# hp_main.net
KiCad netlist of a schematic drawn in Altium Designer
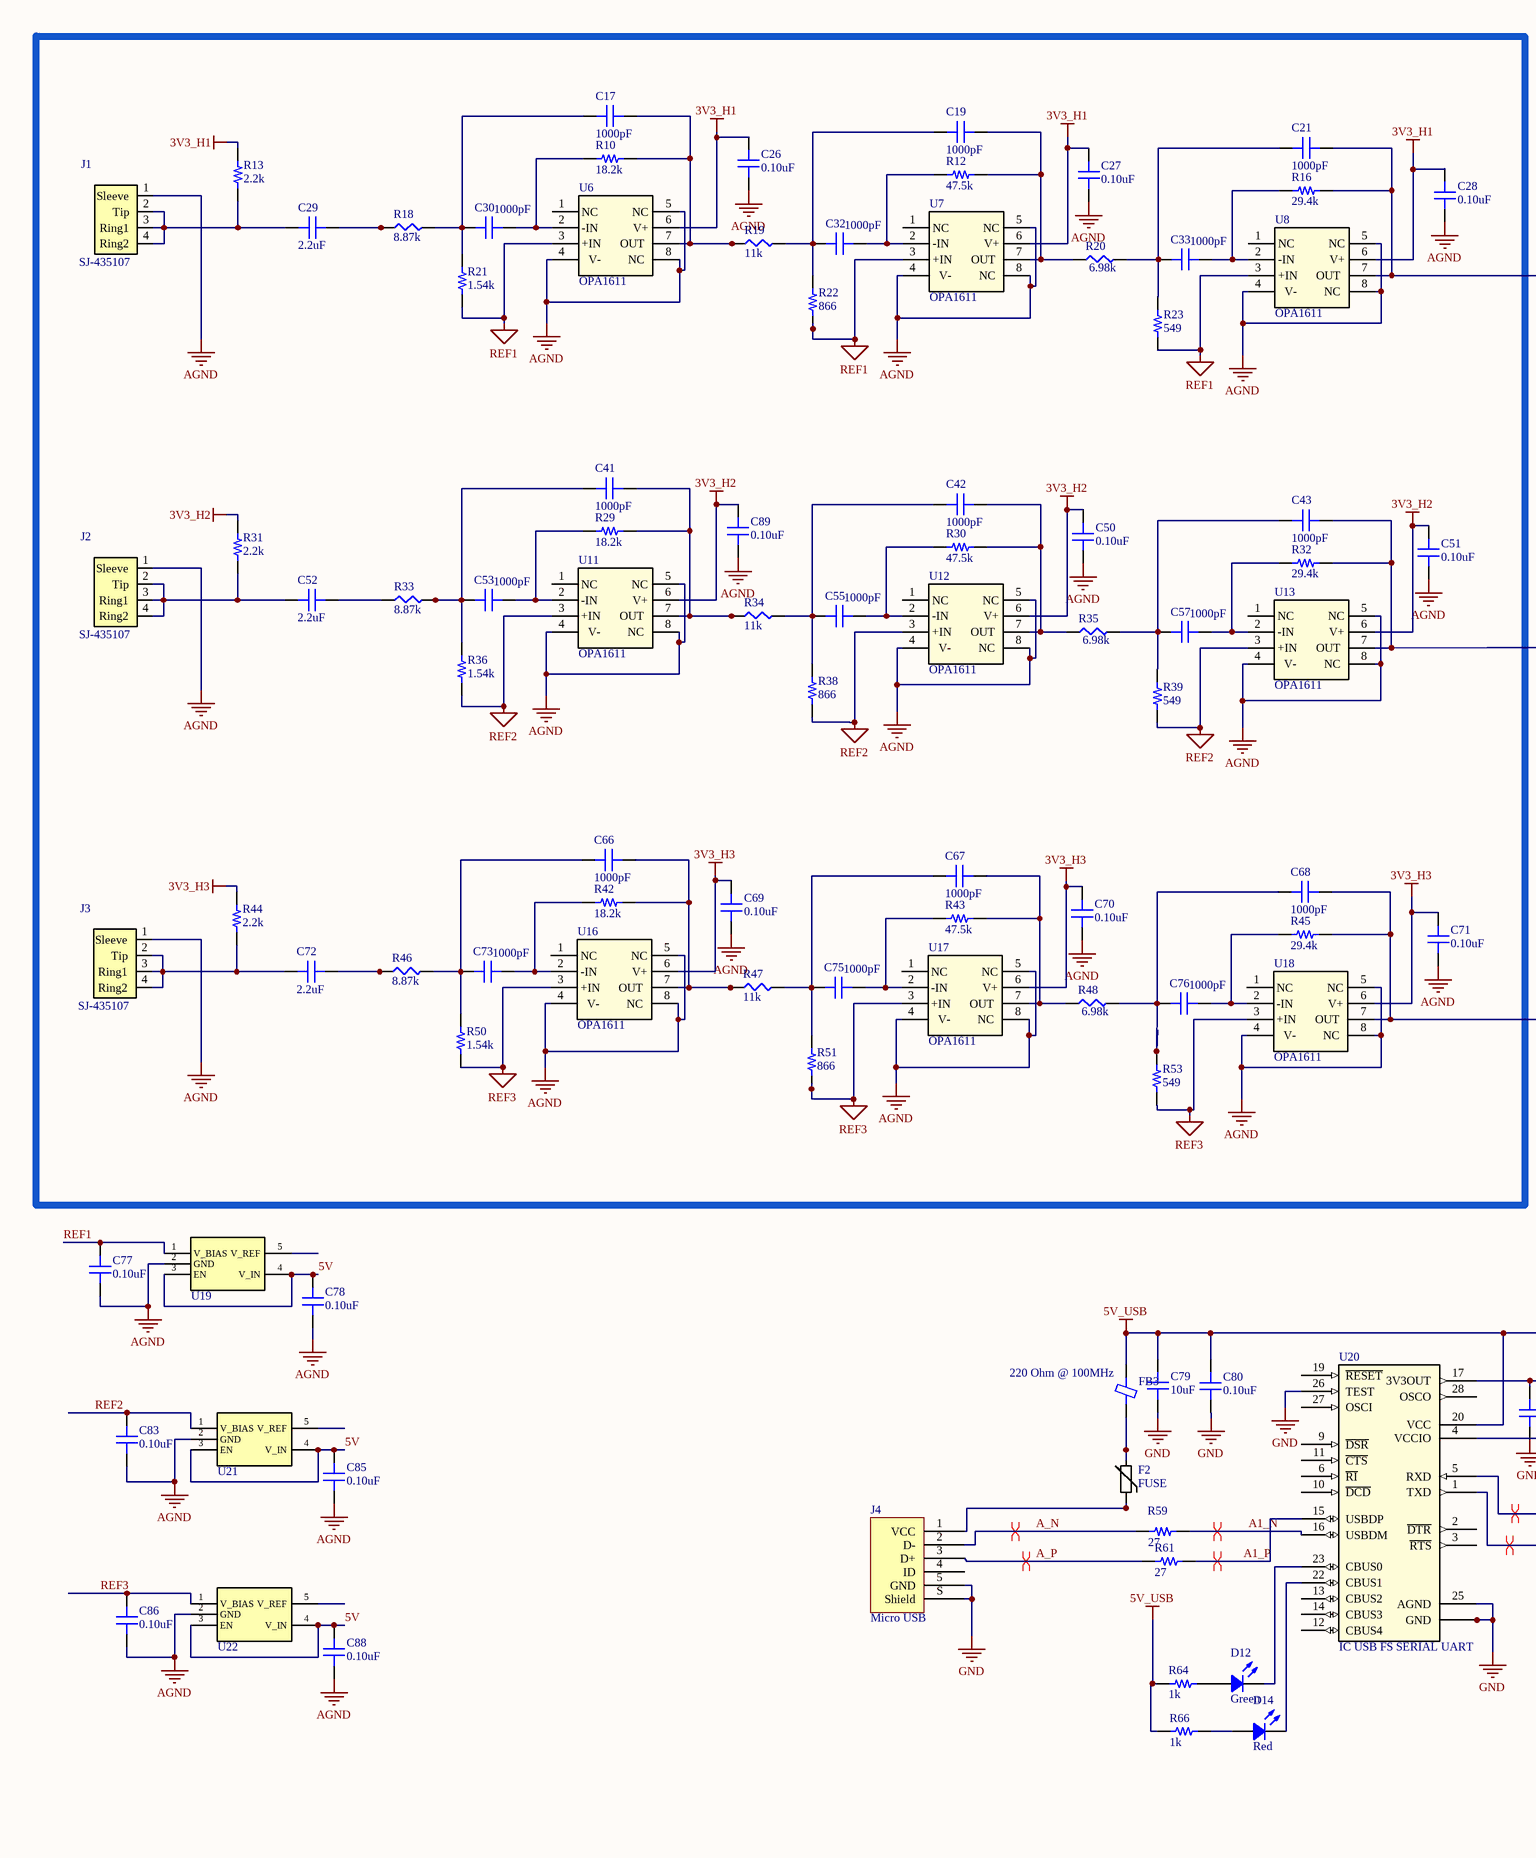
[diagram p0: hp_main.SchDoc, left]
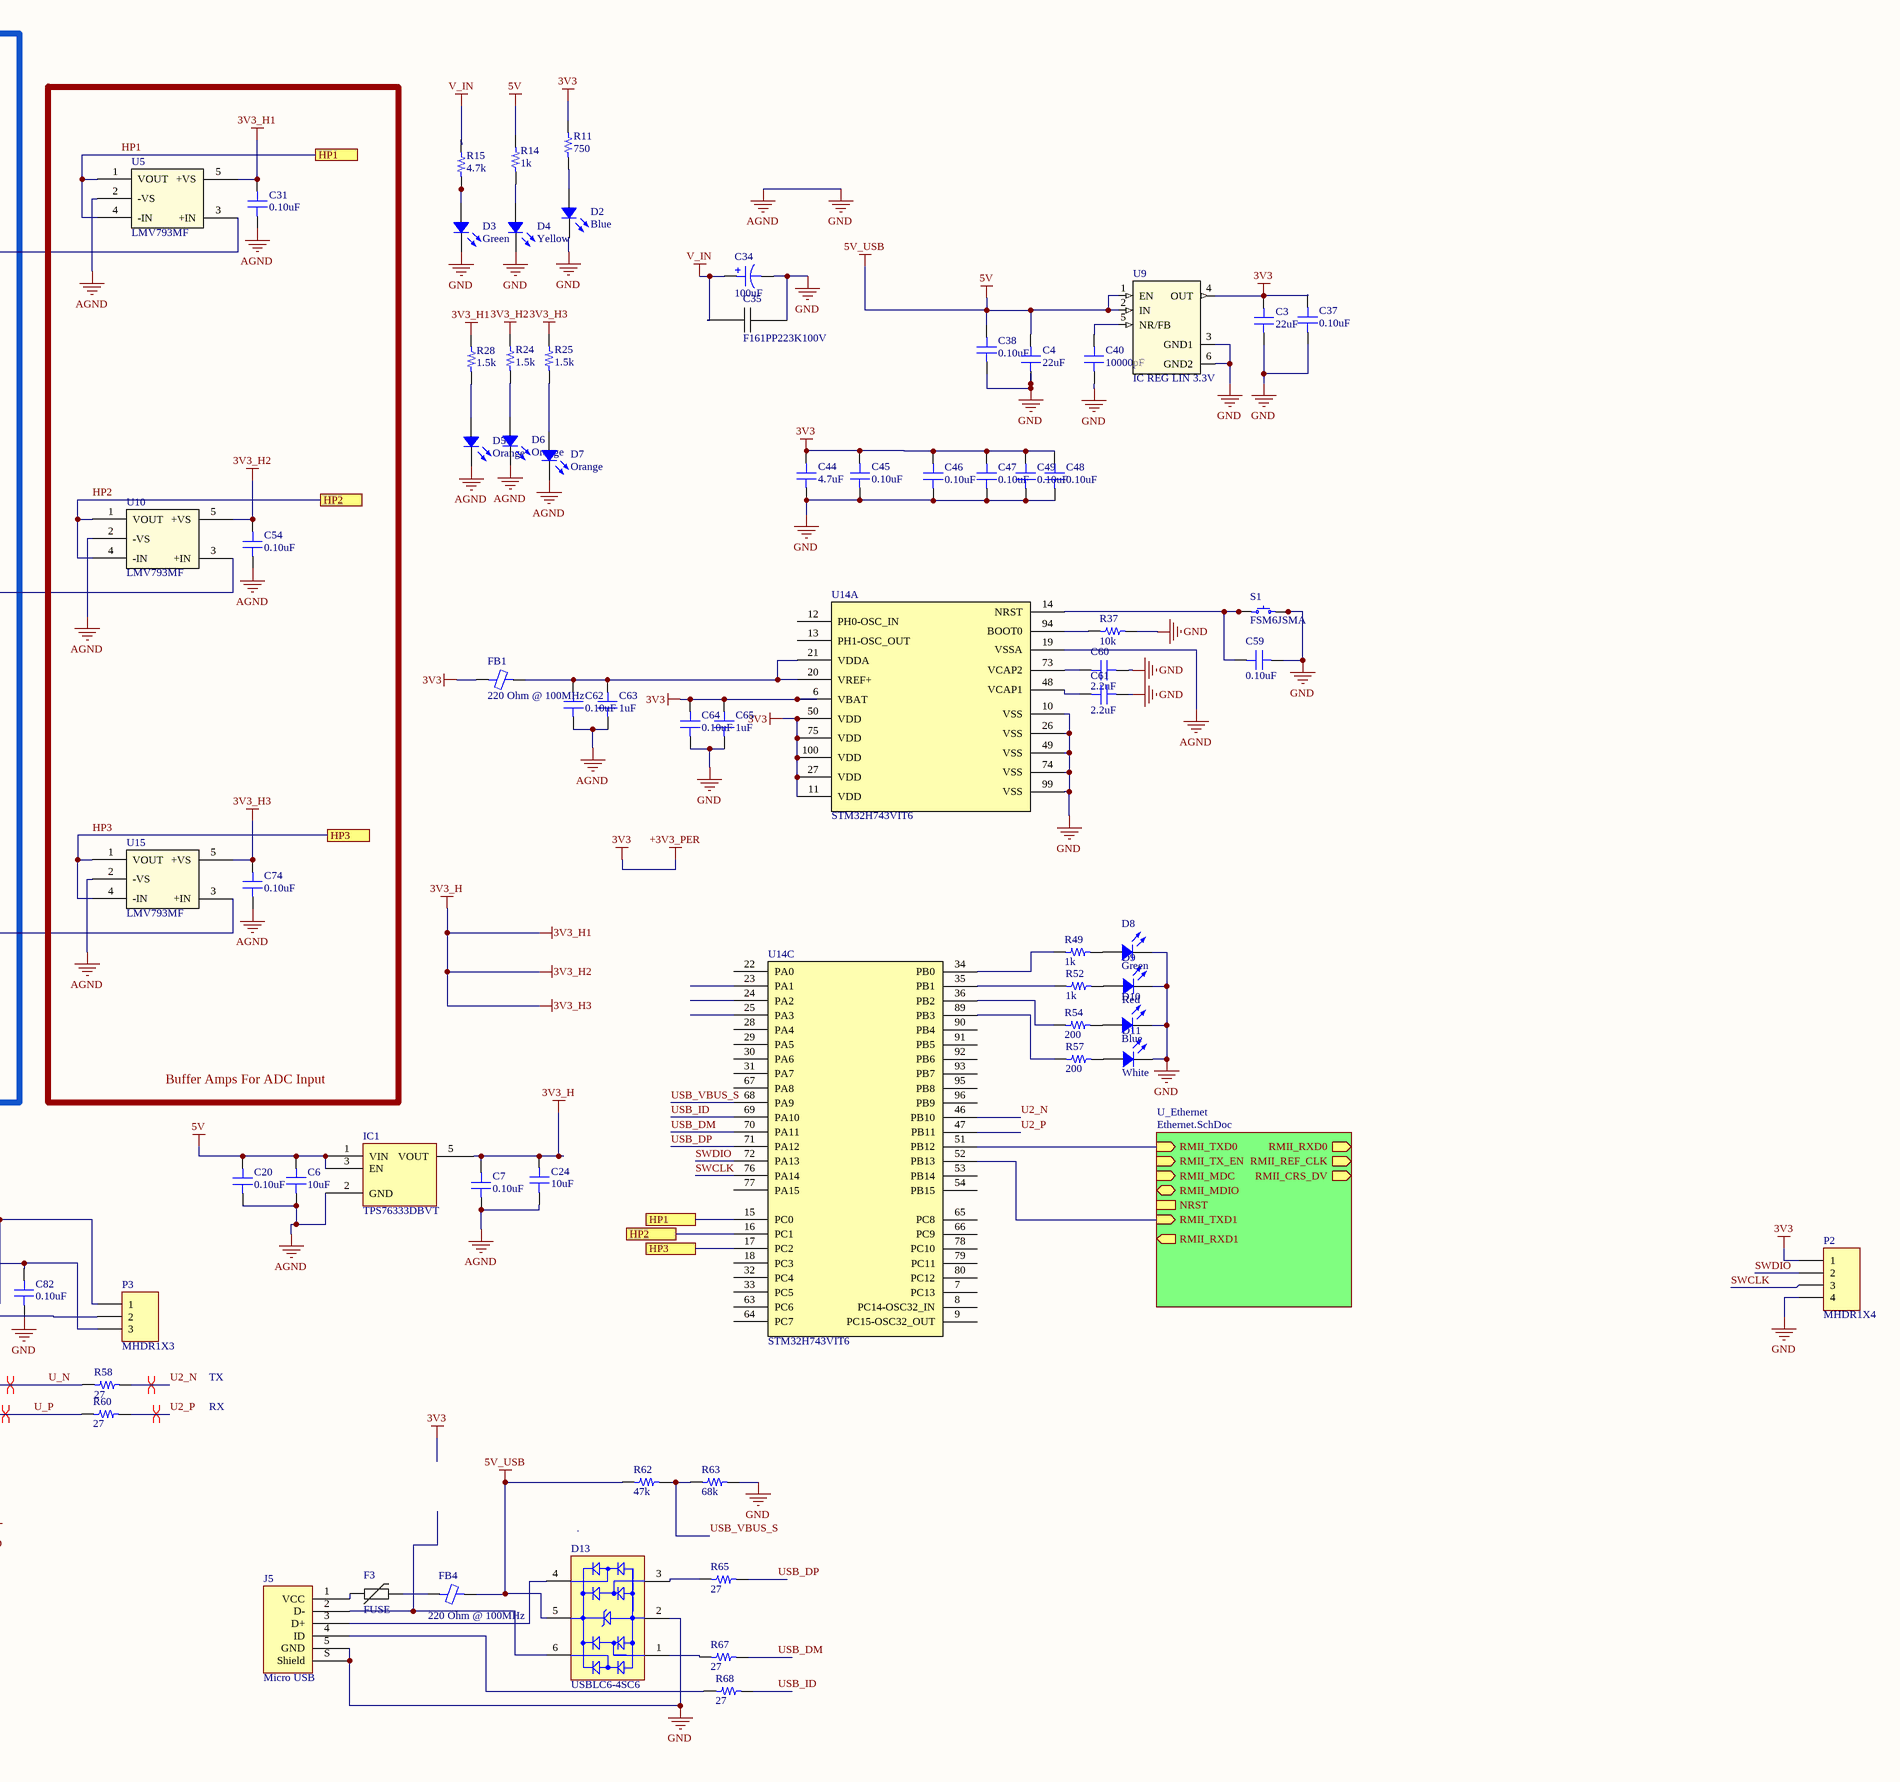
[diagram p1: hp_main.SchDoc, right]

(export (version "E")
  (design (tool "Eeschema 10.0.6"))
  (components
    (comp (ref "C3")
      (value "22uF")
      (footprint "CAP 1206/3216")
      (description "CAP CER 22UF 16V X6S 1206")
      (fields
        (field (name "PART NUMBER") "GRT31CC81C226KE01L")
        (field (name "MANUFACTURER") "Murata Electronics North America")
      )
      (libsource (lib "Celestial Library Database") (part "Capacitor"))
    )
    (comp (ref "C4")
      (value "22uF")
      (footprint "CAP 1206/3216")
      (description "CAP CER 22UF 16V X6S 1206")
      (fields
        (field (name "PART NUMBER") "GRT31CC81C226KE01L")
        (field (name "MANUFACTURER") "Murata Electronics North America")
      )
      (libsource (lib "Celestial Library Database") (part "Capacitor"))
    )
    (comp (ref "C6")
      (value "10uF")
      (footprint "CAP 1206/3216")
      (description "CAP CER 10UF 16V X5R 1206")
      (fields
        (field (name "PART NUMBER") "GRT31CR61C106KE01L")
        (field (name "MANUFACTURER") "Murata Electronics North America")
      )
      (libsource (lib "Celestial Library Database") (part "Capacitor"))
    )
    (comp (ref "C7")
      (value "0.10uF")
      (footprint "CAP 0805/2012")
      (description "CAP CER 0.1UF 100V X7R 0805")
      (fields
        (field (name "PART NUMBER") "CL21B104KCFSFNE")
        (field (name "MANUFACTURER") "Samsung Electro-Mechanics America, Inc.")
      )
      (libsource (lib "Celestial Library Database") (part "Capacitor"))
    )
    (comp (ref "C17")
      (value "1000pF")
      (footprint "CAP 0603/1608")
      (description "CAP CER 1000PF 25V NP0 0603")
      (fields (field (name "PART NUMBER") "C0603C102F3GACTU") (field (name "MANUFACTURER") "Kemet"))
      (libsource (lib "Celestial Library Database") (part "Capacitor"))
    )
    (comp (ref "C19")
      (value "1000pF")
      (footprint "CAP 0603/1608")
      (description "CAP CER 1000PF 25V NP0 0603")
      (fields (field (name "PART NUMBER") "C0603C102F3GACTU") (field (name "MANUFACTURER") "Kemet"))
      (libsource (lib "Celestial Library Database") (part "Capacitor"))
    )
    (comp (ref "C20")
      (value "0.10uF")
      (footprint "CAP 0805/2012")
      (description "CAP CER 0.1UF 100V X7R 0805")
      (fields
        (field (name "PART NUMBER") "CL21B104KCFSFNE")
        (field (name "MANUFACTURER") "Samsung Electro-Mechanics America, Inc.")
      )
      (libsource (lib "Celestial Library Database") (part "Capacitor"))
    )
    (comp (ref "C21")
      (value "1000pF")
      (footprint "CAP 0603/1608")
      (description "CAP CER 1000PF 25V NP0 0603")
      (fields (field (name "PART NUMBER") "C0603C102F3GACTU") (field (name "MANUFACTURER") "Kemet"))
      (libsource (lib "Celestial Library Database") (part "Capacitor"))
    )
    (comp (ref "C24")
      (value "10uF")
      (footprint "CAP 1206/3216")
      (description "CAP CER 10UF 16V X5R 1206")
      (fields
        (field (name "PART NUMBER") "GRT31CR61C106KE01L")
        (field (name "MANUFACTURER") "Murata Electronics North America")
      )
      (libsource (lib "Celestial Library Database") (part "Capacitor"))
    )
    (comp (ref "C26")
      (value "0.10uF")
      (footprint "CAP 0805/2012")
      (description "CAP CER 0.1UF 100V X7R 0805")
      (fields
        (field (name "PART NUMBER") "CL21B104KCFSFNE")
        (field (name "MANUFACTURER") "Samsung Electro-Mechanics America, Inc.")
      )
      (libsource (lib "Celestial Library Database") (part "Capacitor"))
    )
    (comp (ref "C27")
      (value "0.10uF")
      (footprint "CAP 0805/2012")
      (description "CAP CER 0.1UF 100V X7R 0805")
      (fields
        (field (name "PART NUMBER") "CL21B104KCFSFNE")
        (field (name "MANUFACTURER") "Samsung Electro-Mechanics America, Inc.")
      )
      (libsource (lib "Celestial Library Database") (part "Capacitor"))
    )
    (comp (ref "C28")
      (value "0.10uF")
      (footprint "CAP 0805/2012")
      (description "CAP CER 0.1UF 100V X7R 0805")
      (fields
        (field (name "PART NUMBER") "CL21B104KCFSFNE")
        (field (name "MANUFACTURER") "Samsung Electro-Mechanics America, Inc.")
      )
      (libsource (lib "Celestial Library Database") (part "Capacitor"))
    )
    (comp (ref "C29")
      (value "2.2uF")
      (footprint "CAP 0805/2012")
      (description "CAP CER 2.2UF 16V X7R 0805")
      (fields (field (name "PART NUMBER") "C0805C225K4RACTU") (field (name "MANUFACTURER") "Kemet"))
      (libsource (lib "Celestial Library Database") (part "Capacitor"))
    )
    (comp (ref "C30")
      (value "1000pF")
      (footprint "CAP 0603/1608")
      (description "CAP CER 1000PF 25V NP0 0603")
      (fields (field (name "PART NUMBER") "C0603C102F3GACTU") (field (name "MANUFACTURER") "Kemet"))
      (libsource (lib "Celestial Library Database") (part "Capacitor"))
    )
    (comp (ref "C31")
      (value "0.10uF")
      (footprint "CAP 0805/2012")
      (description "CAP CER 0.1UF 100V X7R 0805")
      (fields
        (field (name "PART NUMBER") "CL21B104KCFSFNE")
        (field (name "MANUFACTURER") "Samsung Electro-Mechanics America, Inc.")
      )
      (libsource (lib "Celestial Library Database") (part "Capacitor"))
    )
    (comp (ref "C32")
      (value "1000pF")
      (footprint "CAP 0603/1608")
      (description "CAP CER 1000PF 25V NP0 0603")
      (fields (field (name "PART NUMBER") "C0603C102F3GACTU") (field (name "MANUFACTURER") "Kemet"))
      (libsource (lib "Celestial Library Database") (part "Capacitor"))
    )
    (comp (ref "C33")
      (value "1000pF")
      (footprint "CAP 0603/1608")
      (description "CAP CER 1000PF 25V NP0 0603")
      (fields (field (name "PART NUMBER") "C0603C102F3GACTU") (field (name "MANUFACTURER") "Kemet"))
      (libsource (lib "Celestial Library Database") (part "Capacitor"))
    )
    (comp (ref "C34")
      (value "100uF")
      (footprint "CAP ALUM 6.6MM")
      (description "CAP ALUM 100UF 20% 25V SMD")
      (fields
        (field (name "PART NUMBER") "EEE-1EA101XP")
        (field (name "MANUFACTURER") "Panasonic Electronic Components")
      )
      (libsource (lib "Celestial Library Database") (part "Polarised Capacitor"))
    )
    (comp (ref "C35")
      (value "F161PP223K100V")
      (footprint "F161PP223K100V")
      (libsource (lib "rover_schematic_libraries") (part "F161PP223K100V"))
    )
    (comp (ref "C37")
      (value "0.10uF")
      (footprint "CAP 0805/2012")
      (description "CAP CER 0.1UF 100V X7R 0805")
      (fields
        (field (name "PART NUMBER") "CL21B104KCFSFNE")
        (field (name "MANUFACTURER") "Samsung Electro-Mechanics America, Inc.")
      )
      (libsource (lib "Celestial Library Database") (part "Capacitor"))
    )
    (comp (ref "C38")
      (value "0.10uF")
      (footprint "CAP 0805/2012")
      (description "CAP CER 0.1UF 100V X7R 0805")
      (fields
        (field (name "PART NUMBER") "CL21B104KCFSFNE")
        (field (name "MANUFACTURER") "Samsung Electro-Mechanics America, Inc.")
      )
      (libsource (lib "Celestial Library Database") (part "Capacitor"))
    )
    (comp (ref "C40")
      (value "10000pF")
      (footprint "CAP 0805/2012")
      (description "CAP CER 10000PF 250V X7R 0805")
      (fields
        (field (name "PART NUMBER") "GCJ21BR72E103KXJ3L")
        (field (name "MANUFACTURER") "Murata Electronics North America")
      )
      (libsource (lib "Celestial Library Database") (part "Capacitor"))
    )
    (comp (ref "C41")
      (value "1000pF")
      (footprint "CAP 0603/1608")
      (description "CAP CER 1000PF 25V NP0 0603")
      (fields (field (name "PART NUMBER") "C0603C102F3GACTU") (field (name "MANUFACTURER") "Kemet"))
      (libsource (lib "Celestial Library Database") (part "Capacitor"))
    )
    (comp (ref "C42")
      (value "1000pF")
      (footprint "CAP 0603/1608")
      (description "CAP CER 1000PF 25V NP0 0603")
      (fields (field (name "PART NUMBER") "C0603C102F3GACTU") (field (name "MANUFACTURER") "Kemet"))
      (libsource (lib "Celestial Library Database") (part "Capacitor"))
    )
    (comp (ref "C43")
      (value "1000pF")
      (footprint "CAP 0603/1608")
      (description "CAP CER 1000PF 25V NP0 0603")
      (fields (field (name "PART NUMBER") "C0603C102F3GACTU") (field (name "MANUFACTURER") "Kemet"))
      (libsource (lib "Celestial Library Database") (part "Capacitor"))
    )
    (comp (ref "C44")
      (value "4.7uF")
      (footprint "CAP 0805/2012")
      (description "CAP CER 4.7UF 35V X5R 0805")
      (fields
        (field (name "PART NUMBER") "GRM219R6YA475KA73D")
        (field (name "MANUFACTURER") "Murata Electronics North America")
      )
      (libsource (lib "Celestial Library Database") (part "Capacitor"))
    )
    (comp (ref "C45")
      (value "0.10uF")
      (footprint "CAP 0805/2012")
      (description "CAP CER 0.1UF 100V X7R 0805")
      (fields
        (field (name "PART NUMBER") "CGA4J2X7R2A104K125AE")
        (field (name "MANUFACTURER") "TDK Corporation")
      )
      (libsource (lib "Celestial Library Database") (part "Capacitor"))
    )
    (comp (ref "C46")
      (value "0.10uF")
      (footprint "CAP 0805/2012")
      (description "CAP CER 0.1UF 100V X7R 0805")
      (fields
        (field (name "PART NUMBER") "CGA4J2X7R2A104K125AE")
        (field (name "MANUFACTURER") "TDK Corporation")
      )
      (libsource (lib "Celestial Library Database") (part "Capacitor"))
    )
    (comp (ref "C47")
      (value "0.10uF")
      (footprint "CAP 0805/2012")
      (description "CAP CER 0.1UF 100V X7R 0805")
      (fields
        (field (name "PART NUMBER") "CGA4J2X7R2A104K125AE")
        (field (name "MANUFACTURER") "TDK Corporation")
      )
      (libsource (lib "Celestial Library Database") (part "Capacitor"))
    )
    (comp (ref "C48")
      (value "0.10uF")
      (footprint "CAP 0805/2012")
      (description "CAP CER 0.1UF 100V X7R 0805")
      (fields
        (field (name "PART NUMBER") "CGA4J2X7R2A104K125AE")
        (field (name "MANUFACTURER") "TDK Corporation")
      )
      (libsource (lib "Celestial Library Database") (part "Capacitor"))
    )
    (comp (ref "C49")
      (value "0.10uF")
      (footprint "CAP 0805/2012")
      (description "CAP CER 0.1UF 100V X7R 0805")
      (fields
        (field (name "PART NUMBER") "CGA4J2X7R2A104K125AE")
        (field (name "MANUFACTURER") "TDK Corporation")
      )
      (libsource (lib "Celestial Library Database") (part "Capacitor"))
    )
    (comp (ref "C50")
      (value "0.10uF")
      (footprint "CAP 0805/2012")
      (description "CAP CER 0.1UF 100V X7R 0805")
      (fields
        (field (name "PART NUMBER") "CL21B104KCFSFNE")
        (field (name "MANUFACTURER") "Samsung Electro-Mechanics America, Inc.")
      )
      (libsource (lib "Celestial Library Database") (part "Capacitor"))
    )
    (comp (ref "C51")
      (value "0.10uF")
      (footprint "CAP 0805/2012")
      (description "CAP CER 0.1UF 100V X7R 0805")
      (fields
        (field (name "PART NUMBER") "CL21B104KCFSFNE")
        (field (name "MANUFACTURER") "Samsung Electro-Mechanics America, Inc.")
      )
      (libsource (lib "Celestial Library Database") (part "Capacitor"))
    )
    (comp (ref "C52")
      (value "2.2uF")
      (footprint "CAP 0805/2012")
      (description "CAP CER 2.2UF 16V X7R 0805")
      (fields (field (name "PART NUMBER") "C0805C225K4RACTU") (field (name "MANUFACTURER") "Kemet"))
      (libsource (lib "Celestial Library Database") (part "Capacitor"))
    )
    (comp (ref "C53")
      (value "1000pF")
      (footprint "CAP 0603/1608")
      (description "CAP CER 1000PF 25V NP0 0603")
      (fields (field (name "PART NUMBER") "C0603C102F3GACTU") (field (name "MANUFACTURER") "Kemet"))
      (libsource (lib "Celestial Library Database") (part "Capacitor"))
    )
    (comp (ref "C54")
      (value "0.10uF")
      (footprint "CAP 0805/2012")
      (description "CAP CER 0.1UF 100V X7R 0805")
      (fields
        (field (name "PART NUMBER") "CL21B104KCFSFNE")
        (field (name "MANUFACTURER") "Samsung Electro-Mechanics America, Inc.")
      )
      (libsource (lib "Celestial Library Database") (part "Capacitor"))
    )
    (comp (ref "C55")
      (value "1000pF")
      (footprint "CAP 0603/1608")
      (description "CAP CER 1000PF 25V NP0 0603")
      (fields (field (name "PART NUMBER") "C0603C102F3GACTU") (field (name "MANUFACTURER") "Kemet"))
      (libsource (lib "Celestial Library Database") (part "Capacitor"))
    )
    (comp (ref "C57")
      (value "1000pF")
      (footprint "CAP 0603/1608")
      (description "CAP CER 1000PF 25V NP0 0603")
      (fields (field (name "PART NUMBER") "C0603C102F3GACTU") (field (name "MANUFACTURER") "Kemet"))
      (libsource (lib "Celestial Library Database") (part "Capacitor"))
    )
    (comp (ref "C59")
      (value "0.10uF")
      (footprint "CAP 0805/2012")
      (description "CAP CER 0.1UF 100V X7R 0805")
      (fields
        (field (name "PART NUMBER") "CL21B104KCFSFNE")
        (field (name "MANUFACTURER") "Samsung Electro-Mechanics America, Inc.")
      )
      (libsource (lib "Celestial Library Database") (part "Capacitor"))
    )
    (comp (ref "C60")
      (value "2.2uF")
      (footprint "CAP 0805/2012")
      (description "CAP CER 2.2UF 50V X7R 0805")
      (fields
        (field (name "PART NUMBER") "C2012X7R1H225K125AC")
        (field (name "MANUFACTURER") "TDK Corporation")
      )
      (libsource (lib "Celestial Library Database") (part "Capacitor"))
    )
    (comp (ref "C61")
      (value "2.2uF")
      (footprint "CAP 0805/2012")
      (description "CAP CER 2.2UF 50V X7R 0805")
      (fields
        (field (name "PART NUMBER") "C2012X7R1H225K125AC")
        (field (name "MANUFACTURER") "TDK Corporation")
      )
      (libsource (lib "Celestial Library Database") (part "Capacitor"))
    )
    (comp (ref "C62")
      (value "0.10uF")
      (footprint "CAP 0805/2012")
      (description "CAP CER 0.1UF 100V X7R 0805")
      (fields
        (field (name "PART NUMBER") "CGA4J2X7R2A104K125AE")
        (field (name "MANUFACTURER") "TDK Corporation")
      )
      (libsource (lib "Celestial Library Database") (part "Capacitor"))
    )
    (comp (ref "C63")
      (value "1uF")
      (footprint "CAP 0805/2012")
      (description "CAP CER 1UF 25V X5R 0805")
      (fields
        (field (name "PART NUMBER") "GRM216R61E105KA12D")
        (field (name "MANUFACTURER") "Murata Electronics North America")
      )
      (libsource (lib "Celestial Library Database") (part "Capacitor"))
    )
    (comp (ref "C64")
      (value "0.10uF")
      (footprint "CAP 0805/2012")
      (description "CAP CER 0.1UF 100V X7R 0805")
      (fields
        (field (name "PART NUMBER") "CGA4J2X7R2A104K125AE")
        (field (name "MANUFACTURER") "TDK Corporation")
      )
      (libsource (lib "Celestial Library Database") (part "Capacitor"))
    )
    (comp (ref "C65")
      (value "1uF")
      (footprint "CAP 0805/2012")
      (description "CAP CER 1UF 25V X5R 0805")
      (fields
        (field (name "PART NUMBER") "GRM216R61E105KA12D")
        (field (name "MANUFACTURER") "Murata Electronics North America")
      )
      (libsource (lib "Celestial Library Database") (part "Capacitor"))
    )
    (comp (ref "C66")
      (value "1000pF")
      (footprint "CAP 0603/1608")
      (description "CAP CER 1000PF 25V NP0 0603")
      (fields (field (name "PART NUMBER") "C0603C102F3GACTU") (field (name "MANUFACTURER") "Kemet"))
      (libsource (lib "Celestial Library Database") (part "Capacitor"))
    )
    (comp (ref "C67")
      (value "1000pF")
      (footprint "CAP 0603/1608")
      (description "CAP CER 1000PF 25V NP0 0603")
      (fields (field (name "PART NUMBER") "C0603C102F3GACTU") (field (name "MANUFACTURER") "Kemet"))
      (libsource (lib "Celestial Library Database") (part "Capacitor"))
    )
    (comp (ref "C68")
      (value "1000pF")
      (footprint "CAP 0603/1608")
      (description "CAP CER 1000PF 25V NP0 0603")
      (fields (field (name "PART NUMBER") "C0603C102F3GACTU") (field (name "MANUFACTURER") "Kemet"))
      (libsource (lib "Celestial Library Database") (part "Capacitor"))
    )
    (comp (ref "C69")
      (value "0.10uF")
      (footprint "CAP 0805/2012")
      (description "CAP CER 0.1UF 100V X7R 0805")
      (fields
        (field (name "PART NUMBER") "CL21B104KCFSFNE")
        (field (name "MANUFACTURER") "Samsung Electro-Mechanics America, Inc.")
      )
      (libsource (lib "Celestial Library Database") (part "Capacitor"))
    )
    (comp (ref "C70")
      (value "0.10uF")
      (footprint "CAP 0805/2012")
      (description "CAP CER 0.1UF 100V X7R 0805")
      (fields
        (field (name "PART NUMBER") "CL21B104KCFSFNE")
        (field (name "MANUFACTURER") "Samsung Electro-Mechanics America, Inc.")
      )
      (libsource (lib "Celestial Library Database") (part "Capacitor"))
    )
    (comp (ref "C71")
      (value "0.10uF")
      (footprint "CAP 0805/2012")
      (description "CAP CER 0.1UF 100V X7R 0805")
      (fields
        (field (name "PART NUMBER") "CL21B104KCFSFNE")
        (field (name "MANUFACTURER") "Samsung Electro-Mechanics America, Inc.")
      )
      (libsource (lib "Celestial Library Database") (part "Capacitor"))
    )
    (comp (ref "C72")
      (value "2.2uF")
      (footprint "CAP 0805/2012")
      (description "CAP CER 2.2UF 16V X7R 0805")
      (fields (field (name "PART NUMBER") "C0805C225K4RACTU") (field (name "MANUFACTURER") "Kemet"))
      (libsource (lib "Celestial Library Database") (part "Capacitor"))
    )
    (comp (ref "C73")
      (value "1000pF")
      (footprint "CAP 0603/1608")
      (description "CAP CER 1000PF 25V NP0 0603")
      (fields (field (name "PART NUMBER") "C0603C102F3GACTU") (field (name "MANUFACTURER") "Kemet"))
      (libsource (lib "Celestial Library Database") (part "Capacitor"))
    )
    (comp (ref "C74")
      (value "0.10uF")
      (footprint "CAP 0805/2012")
      (description "CAP CER 0.1UF 100V X7R 0805")
      (fields
        (field (name "PART NUMBER") "CL21B104KCFSFNE")
        (field (name "MANUFACTURER") "Samsung Electro-Mechanics America, Inc.")
      )
      (libsource (lib "Celestial Library Database") (part "Capacitor"))
    )
    (comp (ref "C75")
      (value "1000pF")
      (footprint "CAP 0603/1608")
      (description "CAP CER 1000PF 25V NP0 0603")
      (fields (field (name "PART NUMBER") "C0603C102F3GACTU") (field (name "MANUFACTURER") "Kemet"))
      (libsource (lib "Celestial Library Database") (part "Capacitor"))
    )
    (comp (ref "C76")
      (value "1000pF")
      (footprint "CAP 0603/1608")
      (description "CAP CER 1000PF 25V NP0 0603")
      (fields (field (name "PART NUMBER") "C0603C102F3GACTU") (field (name "MANUFACTURER") "Kemet"))
      (libsource (lib "Celestial Library Database") (part "Capacitor"))
    )
    (comp (ref "C77")
      (value "0.10uF")
      (footprint "CAP 0805/2012")
      (description "CAP CER 0.1UF 100V X7R 0805")
      (fields
        (field (name "PART NUMBER") "CL21B104KCFSFNE")
        (field (name "MANUFACTURER") "Samsung Electro-Mechanics America, Inc.")
      )
      (libsource (lib "Celestial Library Database") (part "Capacitor"))
    )
    (comp (ref "C78")
      (value "0.10uF")
      (footprint "CAP 0805/2012")
      (description "CAP CER 0.1UF 100V X7R 0805")
      (fields
        (field (name "PART NUMBER") "CL21B104KCFSFNE")
        (field (name "MANUFACTURER") "Samsung Electro-Mechanics America, Inc.")
      )
      (libsource (lib "Celestial Library Database") (part "Capacitor"))
    )
    (comp (ref "C79")
      (value "10uF")
      (footprint "CAP 1206/3216")
      (description "CAP CER 10UF 16V X5R 1206")
      (fields
        (field (name "PART NUMBER") "GRT31CR61C106KE01L")
        (field (name "MANUFACTURER") "Murata Electronics North America")
      )
      (libsource (lib "Celestial Library Database") (part "Capacitor"))
    )
    (comp (ref "C80")
      (value "0.10uF")
      (footprint "CAP 0805/2012")
      (description "CAP CER 0.1UF 100V X7R 0805")
      (fields
        (field (name "PART NUMBER") "CGA4J2X7R2A104K125AE")
        (field (name "MANUFACTURER") "TDK Corporation")
      )
      (libsource (lib "Celestial Library Database") (part "Capacitor"))
    )
    (comp (ref "C82")
      (value "0.10uF")
      (footprint "CAP 0805/2012")
      (description "CAP CER 0.1UF 100V X7R 0805")
      (fields
        (field (name "PART NUMBER") "CGA4J2X7R2A104K125AE")
        (field (name "MANUFACTURER") "TDK Corporation")
      )
      (libsource (lib "Celestial Library Database") (part "Capacitor"))
    )
    (comp (ref "C83")
      (value "0.10uF")
      (footprint "CAP 0805/2012")
      (description "CAP CER 0.1UF 100V X7R 0805")
      (fields
        (field (name "PART NUMBER") "CL21B104KCFSFNE")
        (field (name "MANUFACTURER") "Samsung Electro-Mechanics America, Inc.")
      )
      (libsource (lib "Celestial Library Database") (part "Capacitor"))
    )
    (comp (ref "C85")
      (value "0.10uF")
      (footprint "CAP 0805/2012")
      (description "CAP CER 0.1UF 100V X7R 0805")
      (fields
        (field (name "PART NUMBER") "CL21B104KCFSFNE")
        (field (name "MANUFACTURER") "Samsung Electro-Mechanics America, Inc.")
      )
      (libsource (lib "Celestial Library Database") (part "Capacitor"))
    )
    (comp (ref "C86")
      (value "0.10uF")
      (footprint "CAP 0805/2012")
      (description "CAP CER 0.1UF 100V X7R 0805")
      (fields
        (field (name "PART NUMBER") "CL21B104KCFSFNE")
        (field (name "MANUFACTURER") "Samsung Electro-Mechanics America, Inc.")
      )
      (libsource (lib "Celestial Library Database") (part "Capacitor"))
    )
    (comp (ref "C88")
      (value "0.10uF")
      (footprint "CAP 0805/2012")
      (description "CAP CER 0.1UF 100V X7R 0805")
      (fields
        (field (name "PART NUMBER") "CL21B104KCFSFNE")
        (field (name "MANUFACTURER") "Samsung Electro-Mechanics America, Inc.")
      )
      (libsource (lib "Celestial Library Database") (part "Capacitor"))
    )
    (comp (ref "C89")
      (value "0.10uF")
      (footprint "CAP 0805/2012")
      (description "CAP CER 0.1UF 100V X7R 0805")
      (fields
        (field (name "PART NUMBER") "CL21B104KCFSFNE")
        (field (name "MANUFACTURER") "Samsung Electro-Mechanics America, Inc.")
      )
      (libsource (lib "Celestial Library Database") (part "Capacitor"))
    )
    (comp (ref "D2")
      (value "Blue")
      (footprint "LED 0805/2012 BLUE")
      (description "LED BLUE CLEAR 0805 SMD")
      (fields (field (name "PART NUMBER") "LTST-C171TBKT") (field (name "MANUFACTURER") "Lite-On Inc."))
      (libsource (lib "Celestial Library Database") (part "LED"))
    )
    (comp (ref "D3")
      (value "Green")
      (footprint "LED 0805/2012 GREEN")
      (description "LED GREEN CLEAR 0805 SMD")
      (fields (field (name "PART NUMBER") "LTST-C171KGKT") (field (name "MANUFACTURER") "Lite-On Inc."))
      (libsource (lib "Celestial Library Database") (part "LED"))
    )
    (comp (ref "D4")
      (value "Yellow")
      (footprint "LED 0805/2012 YELLOW")
      (description "LED YELLOW CLEAR 0805 SMD")
      (fields (field (name "PART NUMBER") "LTST-C171KSKT") (field (name "MANUFACTURER") "Lite-On Inc."))
      (libsource (lib "Celestial Library Database") (part "LED"))
    )
    (comp (ref "D5")
      (value "Orange")
      (footprint "LED 0603/1608 YELLOW")
      (description "LED ORANGE DIFFUSED 0603 SMD")
      (fields
        (field (name "PART NUMBER") "LO L29K-H2L1-24-Z")
        (field (name "MANUFACTURER") "OSRAM Opto Semiconductors Inc.")
      )
      (libsource (lib "Celestial Library Database") (part "LED"))
    )
    (comp (ref "D6")
      (value "Orange")
      (footprint "LED 0603/1608 YELLOW")
      (description "LED ORANGE DIFFUSED 0603 SMD")
      (fields
        (field (name "PART NUMBER") "LO L29K-H2L1-24-Z")
        (field (name "MANUFACTURER") "OSRAM Opto Semiconductors Inc.")
      )
      (libsource (lib "Celestial Library Database") (part "LED"))
    )
    (comp (ref "D7")
      (value "Orange")
      (footprint "LED 0603/1608 YELLOW")
      (description "LED ORANGE DIFFUSED 0603 SMD")
      (fields
        (field (name "PART NUMBER") "LO L29K-H2L1-24-Z")
        (field (name "MANUFACTURER") "OSRAM Opto Semiconductors Inc.")
      )
      (libsource (lib "Celestial Library Database") (part "LED"))
    )
    (comp (ref "D8")
      (value "Green")
      (footprint "LED 0805/2012 GREEN")
      (description "LED GREEN CLEAR 0805 SMD")
      (fields (field (name "PART NUMBER") "LTST-C171KGKT") (field (name "MANUFACTURER") "Lite-On Inc."))
      (libsource (lib "Celestial Library Database") (part "LED"))
    )
    (comp (ref "D9")
      (value "Red")
      (footprint "LED 0805/2012 RED")
      (description "LED RED CLEAR 0805 SMD")
      (fields (field (name "PART NUMBER") "LTST-C171KRKT") (field (name "MANUFACTURER") "Lite-On Inc."))
      (libsource (lib "Celestial Library Database") (part "LED"))
    )
    (comp (ref "D10")
      (value "Blue")
      (footprint "LED 0805/2012 BLUE")
      (description "LED BLUE CLEAR 0805 SMD")
      (fields (field (name "PART NUMBER") "LTST-C171TBKT") (field (name "MANUFACTURER") "Lite-On Inc."))
      (libsource (lib "Celestial Library Database") (part "LED"))
    )
    (comp (ref "D11")
      (value "White")
      (footprint "LED 0805/2012")
      (description "LED WHITE 0805 SMD")
      (fields (field (name "PART NUMBER") "LTW-170TK") (field (name "MANUFACTURER") "Lite-On Inc."))
      (libsource (lib "Celestial Library Database") (part "LED"))
    )
    (comp (ref "D12")
      (value "Green")
      (footprint "LED 0805/2012 GREEN")
      (description "LED GREEN CLEAR 0805 SMD")
      (fields (field (name "PART NUMBER") "LTST-C171KGKT") (field (name "MANUFACTURER") "Lite-On Inc."))
      (libsource (lib "Celestial Library Database") (part "LED"))
    )
    (comp (ref "D13")
      (value "USBLC6-4SC6")
      (footprint "STM-SOT23-6L_V")
      (fields (field (name "MANUFACTURER") "STMicroelectronics"))
      (libsource (lib "Altium Content Vault") (part "STM-USB_DVI_HDMIULC6-4SC6X-SOT23-6L"))
    )
    (comp (ref "D14")
      (value "Red")
      (footprint "LED 0805/2012 RED")
      (description "LED RED CLEAR 0805 SMD")
      (fields (field (name "PART NUMBER") "LTST-C171KRKT") (field (name "MANUFACTURER") "Lite-On Inc."))
      (libsource (lib "Celestial Library Database") (part "LED"))
    )
    (comp (ref "F2")
      (value "FUSE")
      (footprint "Fuse_0.5A")
      (description "PTC RESET FUSE 6V 500MA 0805")
      (fields
        (field (name "MANUFACTURER") "Littelfuse")
        (field (name "MANUFACTURER PART NUMBER") "0805L050WR")
      )
      (libsource (lib "hydrophone_int_lib") (part "0805L050WR"))
    )
    (comp (ref "F3")
      (value "FUSE")
      (footprint "Fuse_0.5A")
      (description "PTC RESET FUSE 6V 500MA 0805")
      (fields
        (field (name "MANUFACTURER") "Littelfuse")
        (field (name "MANUFACTURER PART NUMBER") "0805L050WR")
      )
      (libsource (lib "hydrophone_int_lib") (part "0805L050WR"))
    )
    (comp (ref "FB1")
      (value "220 Ohm @ 100MHz")
      (footprint "FER 0805/2012")
      (description "FERRITE CHIP 220 OHM 2.0A 0805")
      (fields (field (name "PART NUMBER") "742792022") (field (name "MANUFACTURER") "Wurth Electronics Inc"))
      (libsource (lib "Celestial Library Database") (part "Ferrite Chip"))
    )
    (comp (ref "FB3")
      (value "220 Ohm @ 100MHz")
      (footprint "FER 0805/2012")
      (description "FERRITE CHIP 220 OHM 2.0A 0805")
      (fields (field (name "PART NUMBER") "742792022") (field (name "MANUFACTURER") "Wurth Electronics Inc"))
      (libsource (lib "Celestial Library Database") (part "Ferrite Chip"))
    )
    (comp (ref "FB4")
      (value "220 Ohm @ 100MHz")
      (footprint "FER 0805/2012")
      (description "FERRITE CHIP 220 OHM 2.0A 0805")
      (fields (field (name "PART NUMBER") "742792022") (field (name "MANUFACTURER") "Wurth Electronics Inc"))
      (libsource (lib "Celestial Library Database") (part "Ferrite Chip"))
    )
    (comp (ref "IC1")
      (value "TPS76333DBVT")
      (footprint "TI SOT-23-5 DBV")
      (description "IC REG LDO 3.3V 0.15A SOT23-5")
      (fields (field (name "MANUFACTURER") "Texas Instruments"))
      (libsource (lib "Celestial Library Database") (part "TI TPS763xx"))
    )
    (comp (ref "J1")
      (value "SJ-435107")
      (footprint "CUI_SJ-435107")
      (libsource (lib "hydrophone_int_lib") (part "SJ-435107"))
    )
    (comp (ref "J2")
      (value "SJ-435107")
      (footprint "CUI_SJ-435107")
      (libsource (lib "hydrophone_int_lib") (part "SJ-435107"))
    )
    (comp (ref "J3")
      (value "SJ-435107")
      (footprint "CUI_SJ-435107")
      (libsource (lib "hydrophone_int_lib") (part "SJ-435107"))
    )
    (comp (ref "J4")
      (value "Micro USB")
      (footprint "FCI USB 10118193-0001LF")
      (description "CONN USB MICRO B RECPT SMT R/A")
      (fields (field (name "PART NUMBER") "10118193-0001LF") (field (name "MANUFACTURER") "FCI"))
      (libsource (lib "Celestial Library Database") (part "USB 2.0 Type B Micro"))
    )
    (comp (ref "J5")
      (value "Micro USB")
      (footprint "FCI USB 10118193-0001LF")
      (description "CONN USB MICRO B RECPT SMT R/A")
      (fields (field (name "PART NUMBER") "10118193-0001LF") (field (name "MANUFACTURER") "FCI"))
      (libsource (lib "Celestial Library Database") (part "USB 2.0 Type B Micro"))
    )
    (comp (ref "P2")
      (value "MHDR1X4")
      (footprint "MHDR1X4")
      (description "Header, 4-Pin")
      (fields (field (name "PUBLISHER") "Altium Limited"))
      (libsource (lib "Miscellaneous Connectors") (part "MHDR1X4"))
    )
    (comp (ref "P3")
      (value "MHDR1X3")
      (footprint "MHDR1X3")
      (description "Header, 3-Pin")
      (fields (field (name "PUBLISHER") "Altium Limited"))
      (libsource (lib "Miscellaneous Connectors") (part "MHDR1X3"))
    )
    (comp (ref "R10")
      (value "18.2k")
      (footprint "RES 0603/1608")
      (description "RES SMD 18.2KOHM 0.1% 1/10W 0603")
      (fields
        (field (name "PART NUMBER") "ERA-3AEB1822V")
        (field (name "MANUFACTURER") "Panasonic Electronic Components")
      )
      (libsource (lib "Celestial Library Database") (part "Resistor"))
    )
    (comp (ref "R11")
      (value "750")
      (footprint "RES 0805/2012")
      (description "RES SMD 750 OHM 1% 1/8W 0805")
      (fields
        (field (name "PART NUMBER") "ERJ-6ENF7500V")
        (field (name "MANUFACTURER") "Panasonic Electronic Components")
      )
      (libsource (lib "Celestial Library Database") (part "Resistor"))
    )
    (comp (ref "R12")
      (value "47.5k")
      (footprint "RES 0603/1608")
      (description "RES SMD 47.5KOHM 0.1% 1/10W 0603")
      (fields
        (field (name "PART NUMBER") "ERA-3AEB4752V")
        (field (name "MANUFACTURER") "Panasonic Electronic Components")
      )
      (libsource (lib "Celestial Library Database") (part "Resistor"))
    )
    (comp (ref "R13")
      (value "2.2k")
      (footprint "RES 1206/3216")
      (description "RES SMD 2.2K OHM 1% 1/4W 1206")
      (fields
        (field (name "PART NUMBER") "ERJ-8ENF2201V")
        (field (name "MANUFACTURER") "Panasonic Electronic Components")
      )
      (libsource (lib "Celestial Library Database") (part "Resistor"))
    )
    (comp (ref "R14")
      (value "1k")
      (footprint "RES 0805/2012")
      (description "RES SMD 1K OHM 5% 1/2W 0805")
      (fields
        (field (name "PART NUMBER") "ERJ-P06J102V")
        (field (name "MANUFACTURER") "Panasonic Electronic Components")
      )
      (libsource (lib "Celestial Library Database") (part "Resistor"))
    )
    (comp (ref "R15")
      (value "4.7k")
      (footprint "RES 0805/2012")
      (description "RES SMD 4.7K OHM 5% 1/8W 0805")
      (fields
        (field (name "PART NUMBER") "ERJ-6GEYJ472V")
        (field (name "MANUFACTURER") "Panasonic Electronic Components")
      )
      (libsource (lib "Celestial Library Database") (part "Resistor"))
    )
    (comp (ref "R16")
      (value "29.4k")
      (footprint "RES 0603/1608")
      (description "RES SMD 29.4KOHM 0.1% 1/10W 0603")
      (fields
        (field (name "PART NUMBER") "ERA-3AEB2942V")
        (field (name "MANUFACTURER") "Panasonic Electronic Components")
      )
      (libsource (lib "Celestial Library Database") (part "Resistor"))
    )
    (comp (ref "R18")
      (value "8.87k")
      (footprint "SMD-0603-RES")
      (description "RES SMD 8.87K OHM 1% 1/10W 0603")
      (fields
        (field (name "PART NUMBER") "ERJ-3EKF8871V")
        (field (name "DIGI-KEY PART NUMBER") "P8.87KHCT-ND")
      )
      (libsource (lib "Panasonic_ERJ_0603") (part "ERJ-3EKF8871V"))
    )
    (comp (ref "R19")
      (value "11k")
      (footprint "SMD-0603-RES")
      (description "RES SMD 11K OHM 1% 1/10W 0603")
      (fields
        (field (name "PART NUMBER") "ERJ-3EKF1102V")
        (field (name "DIGI-KEY PART NUMBER") "P11.0KHCT-ND")
      )
      (libsource (lib "Panasonic_ERJ_0603") (part "ERJ-3EKF1102V"))
    )
    (comp (ref "R20")
      (value "6.98k")
      (footprint "SMD-0603-RES")
      (description "RES SMD 6.98K OHM 1% 1/10W 0603")
      (fields
        (field (name "PART NUMBER") "ERJ-3EKF6981V")
        (field (name "DIGI-KEY PART NUMBER") "P6.98KHCT-ND")
      )
      (libsource (lib "Panasonic_ERJ_0603") (part "ERJ-3EKF6981V"))
    )
    (comp (ref "R21")
      (value "1.54k")
      (footprint "RES 0603/1608")
      (description "RES SMD 1.54K OHM 1% 1/10W 0603")
      (fields
        (field (name "PART NUMBER") "ERJ-3EKF1541V")
        (field (name "MANUFACTURER") "Panasonic Electronic Components")
      )
      (libsource (lib "Celestial Library Database") (part "Resistor"))
    )
    (comp (ref "R22")
      (value "866")
      (footprint "RES 0603/1608")
      (description "RES SMD 866 OHM 0.1% 1/10W 0603")
      (fields
        (field (name "PART NUMBER") "ERA-3AEB8660V")
        (field (name "MANUFACTURER") "Panasonic Electronic Components")
      )
      (libsource (lib "Celestial Library Database") (part "Resistor"))
    )
    (comp (ref "R23")
      (value "549")
      (footprint "RES 0603/1608")
      (description "RES SMD 549 OHM 0.5% 1/10W 0603")
      (fields
        (field (name "PART NUMBER") "ERA-3AED5490V")
        (field (name "MANUFACTURER") "Panasonic Electronic Components")
      )
      (libsource (lib "Celestial Library Database") (part "Resistor"))
    )
    (comp (ref "R24")
      (value "1.5k")
      (footprint "RES 0805/2012")
      (description "RES SMD 1.5K OHM 5% 1/8W 0805")
      (fields
        (field (name "PART NUMBER") "ERJ-6GEYJ152V")
        (field (name "MANUFACTURER") "Panasonic Electronic Components")
      )
      (libsource (lib "Celestial Library Database") (part "Resistor"))
    )
    (comp (ref "R25")
      (value "1.5k")
      (footprint "RES 0805/2012")
      (description "RES SMD 1.5K OHM 5% 1/8W 0805")
      (fields
        (field (name "PART NUMBER") "ERJ-6GEYJ152V")
        (field (name "MANUFACTURER") "Panasonic Electronic Components")
      )
      (libsource (lib "Celestial Library Database") (part "Resistor"))
    )
    (comp (ref "R28")
      (value "1.5k")
      (footprint "RES 0805/2012")
      (description "RES SMD 1.5K OHM 5% 1/8W 0805")
      (fields
        (field (name "PART NUMBER") "ERJ-6GEYJ152V")
        (field (name "MANUFACTURER") "Panasonic Electronic Components")
      )
      (libsource (lib "Celestial Library Database") (part "Resistor"))
    )
    (comp (ref "R29")
      (value "18.2k")
      (footprint "RES 0603/1608")
      (description "RES SMD 18.2KOHM 0.1% 1/10W 0603")
      (fields
        (field (name "PART NUMBER") "ERA-3AEB1822V")
        (field (name "MANUFACTURER") "Panasonic Electronic Components")
      )
      (libsource (lib "Celestial Library Database") (part "Resistor"))
    )
    (comp (ref "R30")
      (value "47.5k")
      (footprint "RES 0603/1608")
      (description "RES SMD 47.5KOHM 0.1% 1/10W 0603")
      (fields
        (field (name "PART NUMBER") "ERA-3AEB4752V")
        (field (name "MANUFACTURER") "Panasonic Electronic Components")
      )
      (libsource (lib "Celestial Library Database") (part "Resistor"))
    )
    (comp (ref "R31")
      (value "2.2k")
      (footprint "RES 1206/3216")
      (description "RES SMD 2.2K OHM 1% 1/4W 1206")
      (fields
        (field (name "PART NUMBER") "ERJ-8ENF2201V")
        (field (name "MANUFACTURER") "Panasonic Electronic Components")
      )
      (libsource (lib "Celestial Library Database") (part "Resistor"))
    )
    (comp (ref "R32")
      (value "29.4k")
      (footprint "RES 0603/1608")
      (description "RES SMD 29.4KOHM 0.1% 1/10W 0603")
      (fields
        (field (name "PART NUMBER") "ERA-3AEB2942V")
        (field (name "MANUFACTURER") "Panasonic Electronic Components")
      )
      (libsource (lib "Celestial Library Database") (part "Resistor"))
    )
    (comp (ref "R33")
      (value "8.87k")
      (footprint "SMD-0603-RES")
      (description "RES SMD 8.87K OHM 1% 1/10W 0603")
      (fields
        (field (name "PART NUMBER") "ERJ-3EKF8871V")
        (field (name "DIGI-KEY PART NUMBER") "P8.87KHCT-ND")
      )
      (libsource (lib "Panasonic_ERJ_0603") (part "ERJ-3EKF8871V"))
    )
    (comp (ref "R34")
      (value "11k")
      (footprint "SMD-0603-RES")
      (description "RES SMD 11K OHM 1% 1/10W 0603")
      (fields
        (field (name "PART NUMBER") "ERJ-3EKF1102V")
        (field (name "DIGI-KEY PART NUMBER") "P11.0KHCT-ND")
      )
      (libsource (lib "Panasonic_ERJ_0603") (part "ERJ-3EKF1102V"))
    )
    (comp (ref "R35")
      (value "6.98k")
      (footprint "SMD-0603-RES")
      (description "RES SMD 6.98K OHM 1% 1/10W 0603")
      (fields
        (field (name "PART NUMBER") "ERJ-3EKF6981V")
        (field (name "DIGI-KEY PART NUMBER") "P6.98KHCT-ND")
      )
      (libsource (lib "Panasonic_ERJ_0603") (part "ERJ-3EKF6981V"))
    )
    (comp (ref "R36")
      (value "1.54k")
      (footprint "RES 0603/1608")
      (description "RES SMD 1.54K OHM 1% 1/10W 0603")
      (fields
        (field (name "PART NUMBER") "ERJ-3EKF1541V")
        (field (name "MANUFACTURER") "Panasonic Electronic Components")
      )
      (libsource (lib "Celestial Library Database") (part "Resistor"))
    )
    (comp (ref "R37")
      (value "10k")
      (footprint "RES 0805/2012")
      (description "RES SMD 10K OHM 1% 1/8W 0805")
      (fields
        (field (name "PART NUMBER") "ERJ-6ENF1002V")
        (field (name "MANUFACTURER") "Panasonic Electronic Components")
      )
      (libsource (lib "Celestial Library Database") (part "Resistor"))
    )
    (comp (ref "R38")
      (value "866")
      (footprint "RES 0603/1608")
      (description "RES SMD 866 OHM 0.1% 1/10W 0603")
      (fields
        (field (name "PART NUMBER") "ERA-3AEB8660V")
        (field (name "MANUFACTURER") "Panasonic Electronic Components")
      )
      (libsource (lib "Celestial Library Database") (part "Resistor"))
    )
    (comp (ref "R39")
      (value "549")
      (footprint "RES 0603/1608")
      (description "RES SMD 549 OHM 0.5% 1/10W 0603")
      (fields
        (field (name "PART NUMBER") "ERA-3AED5490V")
        (field (name "MANUFACTURER") "Panasonic Electronic Components")
      )
      (libsource (lib "Celestial Library Database") (part "Resistor"))
    )
    (comp (ref "R42")
      (value "18.2k")
      (footprint "RES 0603/1608")
      (description "RES SMD 18.2KOHM 0.1% 1/10W 0603")
      (fields
        (field (name "PART NUMBER") "ERA-3AEB1822V")
        (field (name "MANUFACTURER") "Panasonic Electronic Components")
      )
      (libsource (lib "Celestial Library Database") (part "Resistor"))
    )
    (comp (ref "R43")
      (value "47.5k")
      (footprint "RES 0603/1608")
      (description "RES SMD 47.5KOHM 0.1% 1/10W 0603")
      (fields
        (field (name "PART NUMBER") "ERA-3AEB4752V")
        (field (name "MANUFACTURER") "Panasonic Electronic Components")
      )
      (libsource (lib "Celestial Library Database") (part "Resistor"))
    )
    (comp (ref "R44")
      (value "2.2k")
      (footprint "RES 1206/3216")
      (description "RES SMD 2.2K OHM 1% 1/4W 1206")
      (fields
        (field (name "PART NUMBER") "ERJ-8ENF2201V")
        (field (name "MANUFACTURER") "Panasonic Electronic Components")
      )
      (libsource (lib "Celestial Library Database") (part "Resistor"))
    )
    (comp (ref "R45")
      (value "29.4k")
      (footprint "RES 0603/1608")
      (description "RES SMD 29.4KOHM 0.1% 1/10W 0603")
      (fields
        (field (name "PART NUMBER") "ERA-3AEB2942V")
        (field (name "MANUFACTURER") "Panasonic Electronic Components")
      )
      (libsource (lib "Celestial Library Database") (part "Resistor"))
    )
    (comp (ref "R46")
      (value "8.87k")
      (footprint "SMD-0603-RES")
      (description "RES SMD 8.87K OHM 1% 1/10W 0603")
      (fields
        (field (name "PART NUMBER") "ERJ-3EKF8871V")
        (field (name "DIGI-KEY PART NUMBER") "P8.87KHCT-ND")
      )
      (libsource (lib "Panasonic_ERJ_0603") (part "ERJ-3EKF8871V"))
    )
    (comp (ref "R47")
      (value "11k")
      (footprint "SMD-0603-RES")
      (description "RES SMD 11K OHM 1% 1/10W 0603")
      (fields
        (field (name "PART NUMBER") "ERJ-3EKF1102V")
        (field (name "DIGI-KEY PART NUMBER") "P11.0KHCT-ND")
      )
      (libsource (lib "Panasonic_ERJ_0603") (part "ERJ-3EKF1102V"))
    )
    (comp (ref "R48")
      (value "6.98k")
      (footprint "SMD-0603-RES")
      (description "RES SMD 6.98K OHM 1% 1/10W 0603")
      (fields
        (field (name "PART NUMBER") "ERJ-3EKF6981V")
        (field (name "DIGI-KEY PART NUMBER") "P6.98KHCT-ND")
      )
      (libsource (lib "Panasonic_ERJ_0603") (part "ERJ-3EKF6981V"))
    )
    (comp (ref "R49")
      (value "1k")
      (footprint "RES 0805/2012")
      (description "RES SMD 1K OHM 1% 1/8W 0805")
      (fields
        (field (name "PART NUMBER") "ERJ-6ENF1001V")
        (field (name "MANUFACTURER") "Panasonic Electronic Components")
      )
      (libsource (lib "Celestial Library Database") (part "Resistor"))
    )
    (comp (ref "R50")
      (value "1.54k")
      (footprint "RES 0603/1608")
      (description "RES SMD 1.54K OHM 1% 1/10W 0603")
      (fields
        (field (name "PART NUMBER") "ERJ-3EKF1541V")
        (field (name "MANUFACTURER") "Panasonic Electronic Components")
      )
      (libsource (lib "Celestial Library Database") (part "Resistor"))
    )
    (comp (ref "R51")
      (value "866")
      (footprint "RES 0603/1608")
      (description "RES SMD 866 OHM 0.1% 1/10W 0603")
      (fields
        (field (name "PART NUMBER") "ERA-3AEB8660V")
        (field (name "MANUFACTURER") "Panasonic Electronic Components")
      )
      (libsource (lib "Celestial Library Database") (part "Resistor"))
    )
    (comp (ref "R52")
      (value "1k")
      (footprint "RES 0805/2012")
      (description "RES SMD 1K OHM 1% 1/8W 0805")
      (fields
        (field (name "PART NUMBER") "ERJ-6ENF1001V")
        (field (name "MANUFACTURER") "Panasonic Electronic Components")
      )
      (libsource (lib "Celestial Library Database") (part "Resistor"))
    )
    (comp (ref "R53")
      (value "549")
      (footprint "RES 0603/1608")
      (description "RES SMD 549 OHM 0.5% 1/10W 0603")
      (fields
        (field (name "PART NUMBER") "ERA-3AED5490V")
        (field (name "MANUFACTURER") "Panasonic Electronic Components")
      )
      (libsource (lib "Celestial Library Database") (part "Resistor"))
    )
    (comp (ref "R54")
      (value "200")
      (footprint "RES 0805/2012")
      (description "RES SMD 200 OHM 1% 1/8W 0805")
      (fields
        (field (name "PART NUMBER") "ERJ-6ENF2000V")
        (field (name "MANUFACTURER") "Panasonic Electronic Components")
      )
      (libsource (lib "Celestial Library Database") (part "Resistor"))
    )
    (comp (ref "R57")
      (value "200")
      (footprint "RES 0805/2012")
      (description "RES SMD 200 OHM 1% 1/8W 0805")
      (fields
        (field (name "PART NUMBER") "ERJ-6ENF2000V")
        (field (name "MANUFACTURER") "Panasonic Electronic Components")
      )
      (libsource (lib "Celestial Library Database") (part "Resistor"))
    )
    (comp (ref "R58")
      (value "27")
      (footprint "RES 0805/2012")
      (description "RES SMD 27 OHM 1% 1/8W 0805")
      (fields
        (field (name "PART NUMBER") "ERJ-6ENF27R0V")
        (field (name "MANUFACTURER") "Panasonic Electronic Components")
      )
      (libsource (lib "Celestial Library Database") (part "Resistor"))
    )
    (comp (ref "R59")
      (value "27")
      (footprint "RES 0805/2012")
      (description "RES SMD 27 OHM 1% 1/8W 0805")
      (fields
        (field (name "PART NUMBER") "ERJ-6ENF27R0V")
        (field (name "MANUFACTURER") "Panasonic Electronic Components")
      )
      (libsource (lib "Celestial Library Database") (part "Resistor"))
    )
    (comp (ref "R60")
      (value "27")
      (footprint "RES 0805/2012")
      (description "RES SMD 27 OHM 1% 1/8W 0805")
      (fields
        (field (name "PART NUMBER") "ERJ-6ENF27R0V")
        (field (name "MANUFACTURER") "Panasonic Electronic Components")
      )
      (libsource (lib "Celestial Library Database") (part "Resistor"))
    )
    (comp (ref "R61")
      (value "27")
      (footprint "RES 0805/2012")
      (description "RES SMD 27 OHM 1% 1/8W 0805")
      (fields
        (field (name "PART NUMBER") "ERJ-6ENF27R0V")
        (field (name "MANUFACTURER") "Panasonic Electronic Components")
      )
      (libsource (lib "Celestial Library Database") (part "Resistor"))
    )
    (comp (ref "R62")
      (value "47k")
      (footprint "RES 0805/2012")
      (description "RES SMD 47K OHM 5% 1/8W 0805")
      (fields
        (field (name "PART NUMBER") "ERJ-6GEYJ473V")
        (field (name "MANUFACTURER") "Panasonic Electronic Components")
      )
      (libsource (lib "Celestial Library Database") (part "Resistor"))
    )
    (comp (ref "R63")
      (value "68k")
      (footprint "RES 0805/2012")
      (description "RES SMD 68K OHM 1% 1/8W 0805")
      (fields
        (field (name "PART NUMBER") "ERJ-6ENF6802V")
        (field (name "MANUFACTURER") "Panasonic Electronic Components")
      )
      (libsource (lib "Celestial Library Database") (part "Resistor"))
    )
    (comp (ref "R64")
      (value "1k")
      (footprint "RES 0805/2012")
      (description "RES SMD 1K OHM 1% 1/8W 0805")
      (fields
        (field (name "PART NUMBER") "ERJ-6ENF1001V")
        (field (name "MANUFACTURER") "Panasonic Electronic Components")
      )
      (libsource (lib "Celestial Library Database") (part "Resistor"))
    )
    (comp (ref "R65")
      (value "27")
      (footprint "RES 0805/2012")
      (description "RES SMD 27 OHM 1% 1/8W 0805")
      (fields
        (field (name "PART NUMBER") "ERJ-6ENF27R0V")
        (field (name "MANUFACTURER") "Panasonic Electronic Components")
      )
      (libsource (lib "Celestial Library Database") (part "Resistor"))
    )
    (comp (ref "R66")
      (value "1k")
      (footprint "RES 0805/2012")
      (description "RES SMD 1K OHM 1% 1/8W 0805")
      (fields
        (field (name "PART NUMBER") "ERJ-6ENF1001V")
        (field (name "MANUFACTURER") "Panasonic Electronic Components")
      )
      (libsource (lib "Celestial Library Database") (part "Resistor"))
    )
    (comp (ref "R67")
      (value "27")
      (footprint "RES 0805/2012")
      (description "RES SMD 27 OHM 1% 1/8W 0805")
      (fields
        (field (name "PART NUMBER") "ERJ-6ENF27R0V")
        (field (name "MANUFACTURER") "Panasonic Electronic Components")
      )
      (libsource (lib "Celestial Library Database") (part "Resistor"))
    )
    (comp (ref "R68")
      (value "27")
      (footprint "RES 0805/2012")
      (description "RES SMD 27 OHM 1% 1/8W 0805")
      (fields
        (field (name "PART NUMBER") "ERJ-6ENF27R0V")
        (field (name "MANUFACTURER") "Panasonic Electronic Components")
      )
      (libsource (lib "Celestial Library Database") (part "Resistor"))
    )
    (comp (ref "S1")
      (value "FSM6JSMA")
      (footprint "TE FSM6JSMA")
      (description "SWITCH TACTILE SPST-NO 0.05A 24V")
      (fields (field (name "MANUFACTURER") "TE Connectivity Alcoswitch Switches"))
      (libsource (lib "Celestial Library Database") (part "SPST-NO 4 PIN"))
    )
    (comp (ref "U5")
      (value "LMV793MF")
      (footprint "SOT23-5")
      (description "General Purpose Amplifier 1 Circuit Rail-to-Rail SOT-23-5")
      (libsource (lib "hydrophone_int_lib") (part "LMV793MF"))
    )
    (comp (ref "U6")
      (value "OPA1611")
      (footprint "OPA1611")
      (description "IC OPAMP AUDIO 80MHZ 8SOIC")
      (libsource (lib "hydrophone_int_lib") (part "OPA1611"))
    )
    (comp (ref "U7")
      (value "OPA1611")
      (footprint "OPA1611")
      (description "IC OPAMP AUDIO 80MHZ 8SOIC")
      (libsource (lib "hydrophone_int_lib") (part "OPA1611"))
    )
    (comp (ref "U8")
      (value "OPA1611")
      (footprint "OPA1611")
      (description "IC OPAMP AUDIO 80MHZ 8SOIC")
      (libsource (lib "hydrophone_int_lib") (part "OPA1611"))
    )
    (comp (ref "U9")
      (value "IC REG LIN 3.3V")
      (footprint "TPS795")
      (description "Linear Voltage Regulator IC Positive Fixed 1 Output 500mA SOT-223-6")
      (libsource (lib "hydrophone_int_lib") (part "TPS795"))
    )
    (comp (ref "U10")
      (value "LMV793MF")
      (footprint "SOT23-5")
      (description "General Purpose Amplifier 1 Circuit Rail-to-Rail SOT-23-5")
      (libsource (lib "hydrophone_int_lib") (part "LMV793MF"))
    )
    (comp (ref "U11")
      (value "OPA1611")
      (footprint "OPA1611")
      (description "IC OPAMP AUDIO 80MHZ 8SOIC")
      (libsource (lib "hydrophone_int_lib") (part "OPA1611"))
    )
    (comp (ref "U12")
      (value "OPA1611")
      (footprint "OPA1611")
      (description "IC OPAMP AUDIO 80MHZ 8SOIC")
      (libsource (lib "hydrophone_int_lib") (part "OPA1611"))
    )
    (comp (ref "U13")
      (value "OPA1611")
      (footprint "OPA1611")
      (description "IC OPAMP AUDIO 80MHZ 8SOIC")
      (libsource (lib "hydrophone_int_lib") (part "OPA1611"))
    )
    (comp (ref "U14")
      (value "STM32H743VIT6")
      (footprint "MCU-LQFP100")
      (description "ARM® Cortex®-M7 STM32H7 Microcontroller IC 32-Bit 400MHz 2MB (2M x 8) FLASH 100-LQFP (14x14)")
      (libsource (lib "hydrophone_int_lib") (part "STM32H743VIT6"))
    )
    (comp (ref "U15")
      (value "LMV793MF")
      (footprint "SOT23-5")
      (description "General Purpose Amplifier 1 Circuit Rail-to-Rail SOT-23-5")
      (libsource (lib "hydrophone_int_lib") (part "LMV793MF"))
    )
    (comp (ref "U16")
      (value "OPA1611")
      (footprint "OPA1611")
      (description "IC OPAMP AUDIO 80MHZ 8SOIC")
      (libsource (lib "hydrophone_int_lib") (part "OPA1611"))
    )
    (comp (ref "U17")
      (value "OPA1611")
      (footprint "OPA1611")
      (description "IC OPAMP AUDIO 80MHZ 8SOIC")
      (libsource (lib "hydrophone_int_lib") (part "OPA1611"))
    )
    (comp (ref "U18")
      (value "OPA1611")
      (footprint "OPA1611")
      (description "IC OPAMP AUDIO 80MHZ 8SOIC")
      (libsource (lib "hydrophone_int_lib") (part "OPA1611"))
    )
    (comp (ref "U19")
      (value "REF2033AIDDCR")
      (footprint "SOT23-5")
      (description "Series Voltage Reference IC ±0.05% 20mA SOT-23-5")
      (libsource (lib "hydrophone_int_lib") (part "REF2033AIDDCR"))
    )
    (comp (ref "U20")
      (value "IC USB FS SERIAL UART")
      (footprint "SSOP-28")
      (description "USB Bridge, USB to UART USB 2.0 UART Interface 28-SSOP")
      (libsource (lib "hydrophone_int_lib") (part "FT232RL"))
    )
    (comp (ref "U21")
      (value "REF2033AIDDCR")
      (footprint "SOT23-5")
      (description "Series Voltage Reference IC ±0.05% 20mA SOT-23-5")
      (libsource (lib "hydrophone_int_lib") (part "REF2033AIDDCR"))
    )
    (comp (ref "U22")
      (value "REF2033AIDDCR")
      (footprint "SOT23-5")
      (description "Series Voltage Reference IC ±0.05% 20mA SOT-23-5")
      (libsource (lib "hydrophone_int_lib") (part "REF2033AIDDCR"))
    )
  )
  (nets
    (net (code "1") (name "+3V3_PER") (class "Default")
      (node (ref "C3") (pin "2") (pinfunction "2_2") (pintype "passive"))
      (node (ref "C37") (pin "2") (pinfunction "2_2") (pintype "passive"))
      (node (ref "C44") (pin "2") (pinfunction "2_2") (pintype "passive"))
      (node (ref "C45") (pin "2") (pinfunction "2_2") (pintype "passive"))
      (node (ref "C46") (pin "2") (pinfunction "2_2") (pintype "passive"))
      (node (ref "C47") (pin "2") (pinfunction "2_2") (pintype "passive"))
      (node (ref "C48") (pin "2") (pinfunction "2_2") (pintype "passive"))
      (node (ref "C49") (pin "2") (pinfunction "2_2") (pintype "passive"))
      (node (ref "C64") (pin "2") (pinfunction "2_2") (pintype "passive"))
      (node (ref "C65") (pin "2") (pinfunction "2_2") (pintype "passive"))
      (node (ref "FB1") (pin "2") (pinfunction "2_2") (pintype "passive"))
      (node (ref "P2") (pin "1") (pinfunction "1_1") (pintype "passive"))
      (node (ref "R11") (pin "1") (pinfunction "1_1") (pintype "passive"))
      (node (ref "U14") (pin "100") (pinfunction "VDD_100") (pintype "passive"))
      (node (ref "U14") (pin "11") (pinfunction "VDD_11") (pintype "passive"))
      (node (ref "U14") (pin "27") (pinfunction "VDD_27") (pintype "passive"))
      (node (ref "U14") (pin "50") (pinfunction "VDD_50") (pintype "passive"))
      (node (ref "U14") (pin "6") (pinfunction "VBAT_6") (pintype "passive"))
      (node (ref "U14") (pin "75") (pinfunction "VDD_75") (pintype "passive"))
      (node (ref "U9") (pin "4") (pinfunction "OUT_4") (pintype "output"))
    )
    (net (code "2") (name "/A1_N") (class "Default")
      (node (ref "R59") (pin "2") (pinfunction "2_2") (pintype "passive"))
      (node (ref "U20") (pin "16") (pinfunction "USBDM_16") (pintype "bidirectional"))
    )
    (net (code "3") (name "/A1_P") (class "Default")
      (node (ref "R61") (pin "2") (pinfunction "2_2") (pintype "passive"))
      (node (ref "U20") (pin "15") (pinfunction "USBDP_15") (pintype "bidirectional"))
    )
    (net (code "4") (name "/A_N") (class "Default")
      (node (ref "J4") (pin "2") (pinfunction "D-_2") (pintype "passive"))
      (node (ref "R59") (pin "1") (pinfunction "1_1") (pintype "passive"))
    )
    (net (code "5") (name "/A_P") (class "Default")
      (node (ref "J4") (pin "3") (pinfunction "D+_3") (pintype "passive"))
      (node (ref "R61") (pin "1") (pinfunction "1_1") (pintype "passive"))
    )
    (net (code "6") (name "/HP1") (class "Default")
      (node (ref "U14") (pin "15") (pinfunction "PC0_15") (pintype "passive"))
      (node (ref "U5") (pin "1") (pinfunction "VOUT_1") (pintype "passive"))
      (node (ref "U5") (pin "4") (pinfunction "-IN_4") (pintype "passive"))
    )
    (net (code "7") (name "/HP2") (class "Default")
      (node (ref "U10") (pin "1") (pinfunction "VOUT_1") (pintype "passive"))
      (node (ref "U10") (pin "4") (pinfunction "-IN_4") (pintype "passive"))
      (node (ref "U14") (pin "16") (pinfunction "PC1_16") (pintype "passive"))
    )
    (net (code "8") (name "/HP3") (class "Default")
      (node (ref "U14") (pin "17") (pinfunction "PC2_17") (pintype "passive"))
      (node (ref "U15") (pin "1") (pinfunction "VOUT_1") (pintype "passive"))
      (node (ref "U15") (pin "4") (pinfunction "-IN_4") (pintype "passive"))
    )
    (net (code "16") (name "/RMII_TXD0") (class "Default")
      (node (ref "U14") (pin "51") (pinfunction "PB12_51") (pintype "passive"))
    )
    (net (code "17") (name "/RMII_TXD1") (class "Default")
      (node (ref "U14") (pin "52") (pinfunction "PB13_52") (pintype "passive"))
    )
    (net (code "19") (name "/SWCLK") (class "Default")
      (node (ref "P2") (pin "3") (pinfunction "3_3") (pintype "passive"))
      (node (ref "U14") (pin "76") (pinfunction "PA14_76") (pintype "passive"))
    )
    (net (code "20") (name "/SWDIO") (class "Default")
      (node (ref "P2") (pin "2") (pinfunction "2_2") (pintype "passive"))
      (node (ref "U14") (pin "72") (pinfunction "PA13_72") (pintype "passive"))
    )
    (net (code "21") (name "/U2_N") (class "Default")
      (node (ref "R58") (pin "2") (pinfunction "2_2") (pintype "passive"))
      (node (ref "U14") (pin "46") (pinfunction "PB10_46") (pintype "passive"))
    )
    (net (code "22") (name "/U2_P") (class "Default")
      (node (ref "R60") (pin "2") (pinfunction "2_2") (pintype "passive"))
      (node (ref "U14") (pin "47") (pinfunction "PB11_47") (pintype "passive"))
    )
    (net (code "23") (name "/USB_DM") (class "Default")
      (node (ref "R67") (pin "2") (pinfunction "2_2") (pintype "passive"))
      (node (ref "U14") (pin "70") (pinfunction "PA11_70") (pintype "passive"))
    )
    (net (code "24") (name "/USB_DP") (class "Default")
      (node (ref "R65") (pin "2") (pinfunction "2_2") (pintype "passive"))
      (node (ref "U14") (pin "71") (pinfunction "PA12_71") (pintype "passive"))
    )
    (net (code "25") (name "/USB_ID") (class "Default")
      (node (ref "R68") (pin "2") (pinfunction "2_2") (pintype "passive"))
      (node (ref "U14") (pin "69") (pinfunction "PA10_69") (pintype "passive"))
    )
    (net (code "26") (name "/USB_VBUS_S") (class "Default")
      (node (ref "R62") (pin "2") (pinfunction "2_2") (pintype "passive"))
      (node (ref "R63") (pin "1") (pinfunction "1_1") (pintype "passive"))
      (node (ref "U14") (pin "68") (pinfunction "PA9_68") (pintype "passive"))
    )
    (net (code "27") (name "/U_N") (class "Default")
      (node (ref "R58") (pin "1") (pinfunction "1_1") (pintype "passive"))
      (node (ref "U20") (pin "5") (pinfunction "RXD_5") (pintype "input"))
    )
    (net (code "28") (name "/U_P") (class "Default")
      (node (ref "R60") (pin "1") (pinfunction "1_1") (pintype "passive"))
      (node (ref "U20") (pin "1") (pinfunction "TXD_1") (pintype "output"))
    )
    (net (code "29") (name "3V3_H") (class "Default")
      (node (ref "C24") (pin "1") (pinfunction "1_1") (pintype "passive"))
      (node (ref "C26") (pin "2") (pinfunction "2_2") (pintype "passive"))
      (node (ref "C27") (pin "2") (pinfunction "2_2") (pintype "passive"))
      (node (ref "C28") (pin "2") (pinfunction "2_2") (pintype "passive"))
      (node (ref "C31") (pin "2") (pinfunction "2_2") (pintype "passive"))
      (node (ref "C50") (pin "2") (pinfunction "2_2") (pintype "passive"))
      (node (ref "C51") (pin "2") (pinfunction "2_2") (pintype "passive"))
      (node (ref "C54") (pin "2") (pinfunction "2_2") (pintype "passive"))
      (node (ref "C69") (pin "2") (pinfunction "2_2") (pintype "passive"))
      (node (ref "C7") (pin "2") (pinfunction "2_2") (pintype "passive"))
      (node (ref "C70") (pin "2") (pinfunction "2_2") (pintype "passive"))
      (node (ref "C71") (pin "2") (pinfunction "2_2") (pintype "passive"))
      (node (ref "C74") (pin "2") (pinfunction "2_2") (pintype "passive"))
      (node (ref "C89") (pin "2") (pinfunction "2_2") (pintype "passive"))
      (node (ref "IC1") (pin "5") (pinfunction "VOUT_5") (pintype "passive"))
      (node (ref "R13") (pin "1") (pinfunction "1_1") (pintype "passive"))
      (node (ref "R24") (pin "2") (pinfunction "2_2") (pintype "passive"))
      (node (ref "R25") (pin "2") (pinfunction "2_2") (pintype "passive"))
      (node (ref "R28") (pin "2") (pinfunction "2_2") (pintype "passive"))
      (node (ref "R31") (pin "1") (pinfunction "1_1") (pintype "passive"))
      (node (ref "R44") (pin "1") (pinfunction "1_1") (pintype "passive"))
      (node (ref "U10") (pin "5") (pinfunction "+VS_5") (pintype "power_in"))
      (node (ref "U11") (pin "6") (pinfunction "V+_6") (pintype "passive"))
      (node (ref "U12") (pin "6") (pinfunction "V+_6") (pintype "passive"))
      (node (ref "U13") (pin "6") (pinfunction "V+_6") (pintype "passive"))
      (node (ref "U15") (pin "5") (pinfunction "+VS_5") (pintype "power_in"))
      (node (ref "U16") (pin "6") (pinfunction "V+_6") (pintype "passive"))
      (node (ref "U17") (pin "6") (pinfunction "V+_6") (pintype "passive"))
      (node (ref "U18") (pin "6") (pinfunction "V+_6") (pintype "passive"))
      (node (ref "U5") (pin "5") (pinfunction "+VS_5") (pintype "power_in"))
      (node (ref "U6") (pin "6") (pinfunction "V+_6") (pintype "passive"))
      (node (ref "U7") (pin "6") (pinfunction "V+_6") (pintype "passive"))
      (node (ref "U8") (pin "6") (pinfunction "V+_6") (pintype "passive"))
    )
    (net (code "30") (name "5V") (class "Default")
      (node (ref "C20") (pin "2") (pinfunction "2_2") (pintype "passive"))
      (node (ref "C38") (pin "2") (pinfunction "2_2") (pintype "passive"))
      (node (ref "C4") (pin "2") (pinfunction "2_2") (pintype "passive"))
      (node (ref "C6") (pin "1") (pinfunction "1_1") (pintype "passive"))
      (node (ref "C78") (pin "2") (pinfunction "2_2") (pintype "passive"))
      (node (ref "C79") (pin "2") (pinfunction "2_2") (pintype "passive"))
      (node (ref "C80") (pin "2") (pinfunction "2_2") (pintype "passive"))
      (node (ref "C85") (pin "2") (pinfunction "2_2") (pintype "passive"))
      (node (ref "C88") (pin "2") (pinfunction "2_2") (pintype "passive"))
      (node (ref "D13") (pin "5") (pinfunction "VBUS_5") (pintype "passive"))
      (node (ref "FB3") (pin "2") (pinfunction "2_2") (pintype "passive"))
      (node (ref "FB4") (pin "1") (pinfunction "1_1") (pintype "passive"))
      (node (ref "IC1") (pin "1") (pinfunction "VIN_1") (pintype "passive"))
      (node (ref "IC1") (pin "3") (pinfunction "EN_3") (pintype "passive"))
      (node (ref "P3") (pin "1") (pinfunction "1_1") (pintype "passive"))
      (node (ref "R14") (pin "2") (pinfunction "2_2") (pintype "passive"))
      (node (ref "R62") (pin "1") (pinfunction "1_1") (pintype "passive"))
      (node (ref "R64") (pin "1") (pinfunction "1_1") (pintype "passive"))
      (node (ref "R66") (pin "1") (pinfunction "1_1") (pintype "passive"))
      (node (ref "U19") (pin "3") (pinfunction "EN_3") (pintype "passive"))
      (node (ref "U19") (pin "4") (pinfunction "V_IN_4") (pintype "passive"))
      (node (ref "U20") (pin "20") (pinfunction "VCC_20") (pintype "power_in"))
      (node (ref "U21") (pin "3") (pinfunction "EN_3") (pintype "passive"))
      (node (ref "U21") (pin "4") (pinfunction "V_IN_4") (pintype "passive"))
      (node (ref "U22") (pin "3") (pinfunction "EN_3") (pintype "passive"))
      (node (ref "U22") (pin "4") (pinfunction "V_IN_4") (pintype "passive"))
      (node (ref "U9") (pin "1") (pinfunction "EN_1") (pintype "input"))
      (node (ref "U9") (pin "2") (pinfunction "IN_2") (pintype "input"))
    )
    (net (code "31") (name "AGND") (class "Default")
      (node (ref "C20") (pin "1") (pinfunction "1_1") (pintype "passive"))
      (node (ref "C24") (pin "2") (pinfunction "2_2") (pintype "passive"))
      (node (ref "C26") (pin "1") (pinfunction "1_1") (pintype "passive"))
      (node (ref "C27") (pin "1") (pinfunction "1_1") (pintype "passive"))
      (node (ref "C28") (pin "1") (pinfunction "1_1") (pintype "passive"))
      (node (ref "C3") (pin "1") (pinfunction "1_1") (pintype "passive"))
      (node (ref "C31") (pin "1") (pinfunction "1_1") (pintype "passive"))
      (node (ref "C34") (pin "2") (pinfunction "2_2") (pintype "passive"))
      (node (ref "C35") (pin "2") (pinfunction "2_2") (pintype "passive"))
      (node (ref "C37") (pin "1") (pinfunction "1_1") (pintype "passive"))
      (node (ref "C38") (pin "1") (pinfunction "1_1") (pintype "passive"))
      (node (ref "C4") (pin "1") (pinfunction "1_1") (pintype "passive"))
      (node (ref "C40") (pin "1") (pinfunction "1_1") (pintype "passive"))
      (node (ref "C44") (pin "1") (pinfunction "1_1") (pintype "passive"))
      (node (ref "C45") (pin "1") (pinfunction "1_1") (pintype "passive"))
      (node (ref "C46") (pin "1") (pinfunction "1_1") (pintype "passive"))
      (node (ref "C47") (pin "1") (pinfunction "1_1") (pintype "passive"))
      (node (ref "C48") (pin "1") (pinfunction "1_1") (pintype "passive"))
      (node (ref "C49") (pin "1") (pinfunction "1_1") (pintype "passive"))
      (node (ref "C50") (pin "1") (pinfunction "1_1") (pintype "passive"))
      (node (ref "C51") (pin "1") (pinfunction "1_1") (pintype "passive"))
      (node (ref "C54") (pin "1") (pinfunction "1_1") (pintype "passive"))
      (node (ref "C59") (pin "2") (pinfunction "2_2") (pintype "passive"))
      (node (ref "C6") (pin "2") (pinfunction "2_2") (pintype "passive"))
      (node (ref "C60") (pin "2") (pinfunction "2_2") (pintype "passive"))
      (node (ref "C61") (pin "2") (pinfunction "2_2") (pintype "passive"))
      (node (ref "C62") (pin "1") (pinfunction "1_1") (pintype "passive"))
      (node (ref "C63") (pin "1") (pinfunction "1_1") (pintype "passive"))
      (node (ref "C64") (pin "1") (pinfunction "1_1") (pintype "passive"))
      (node (ref "C65") (pin "1") (pinfunction "1_1") (pintype "passive"))
      (node (ref "C69") (pin "1") (pinfunction "1_1") (pintype "passive"))
      (node (ref "C7") (pin "1") (pinfunction "1_1") (pintype "passive"))
      (node (ref "C70") (pin "1") (pinfunction "1_1") (pintype "passive"))
      (node (ref "C71") (pin "1") (pinfunction "1_1") (pintype "passive"))
      (node (ref "C74") (pin "1") (pinfunction "1_1") (pintype "passive"))
      (node (ref "C77") (pin "1") (pinfunction "1_1") (pintype "passive"))
      (node (ref "C78") (pin "1") (pinfunction "1_1") (pintype "passive"))
      (node (ref "C79") (pin "1") (pinfunction "1_1") (pintype "passive"))
      (node (ref "C80") (pin "1") (pinfunction "1_1") (pintype "passive"))
      (node (ref "C82") (pin "1") (pinfunction "1_1") (pintype "passive"))
      (node (ref "C83") (pin "1") (pinfunction "1_1") (pintype "passive"))
      (node (ref "C85") (pin "1") (pinfunction "1_1") (pintype "passive"))
      (node (ref "C86") (pin "1") (pinfunction "1_1") (pintype "passive"))
      (node (ref "C88") (pin "1") (pinfunction "1_1") (pintype "passive"))
      (node (ref "C89") (pin "1") (pinfunction "1_1") (pintype "passive"))
      (node (ref "D10") (pin "2") (pinfunction "2_2") (pintype "passive"))
      (node (ref "D11") (pin "2") (pinfunction "2_2") (pintype "passive"))
      (node (ref "D13") (pin "2") (pinfunction "GND_2") (pintype "passive"))
      (node (ref "D2") (pin "2") (pinfunction "2_2") (pintype "passive"))
      (node (ref "D3") (pin "2") (pinfunction "2_2") (pintype "passive"))
      (node (ref "D4") (pin "2") (pinfunction "2_2") (pintype "passive"))
      (node (ref "D5") (pin "2") (pinfunction "2_2") (pintype "passive"))
      (node (ref "D6") (pin "2") (pinfunction "2_2") (pintype "passive"))
      (node (ref "D7") (pin "2") (pinfunction "2_2") (pintype "passive"))
      (node (ref "D8") (pin "2") (pinfunction "2_2") (pintype "passive"))
      (node (ref "D9") (pin "2") (pinfunction "2_2") (pintype "passive"))
      (node (ref "IC1") (pin "2") (pinfunction "GND_2") (pintype "passive"))
      (node (ref "J1") (pin "1") (pinfunction "Sleeve_1") (pintype "passive"))
      (node (ref "J2") (pin "1") (pinfunction "Sleeve_1") (pintype "passive"))
      (node (ref "J3") (pin "1") (pinfunction "Sleeve_1") (pintype "passive"))
      (node (ref "J4") (pin "5") (pinfunction "GND_5") (pintype "passive"))
      (node (ref "J4") (pin "S") (pinfunction "Shield_S") (pintype "passive"))
      (node (ref "J5") (pin "5") (pinfunction "GND_5") (pintype "passive"))
      (node (ref "J5") (pin "S") (pinfunction "Shield_S") (pintype "passive"))
      (node (ref "P2") (pin "4") (pinfunction "4_4") (pintype "passive"))
      (node (ref "R37") (pin "1") (pinfunction "1_1") (pintype "passive"))
      (node (ref "R63") (pin "2") (pinfunction "2_2") (pintype "passive"))
      (node (ref "S1") (pin "3") (pinfunction "3_3") (pintype "passive"))
      (node (ref "S1") (pin "4") (pinfunction "4_4") (pintype "passive"))
      (node (ref "U10") (pin "2") (pinfunction "-VS_2") (pintype "power_in"))
      (node (ref "U11") (pin "4") (pinfunction "V-_4") (pintype "passive"))
      (node (ref "U11") (pin "5") (pinfunction "NC_5") (pintype "passive"))
      (node (ref "U11") (pin "8") (pinfunction "NC_8") (pintype "passive"))
      (node (ref "U12") (pin "4") (pinfunction "V-_4") (pintype "passive"))
      (node (ref "U12") (pin "5") (pinfunction "NC_5") (pintype "passive"))
      (node (ref "U12") (pin "8") (pinfunction "NC_8") (pintype "passive"))
      (node (ref "U13") (pin "4") (pinfunction "V-_4") (pintype "passive"))
      (node (ref "U13") (pin "5") (pinfunction "NC_5") (pintype "passive"))
      (node (ref "U13") (pin "8") (pinfunction "NC_8") (pintype "passive"))
      (node (ref "U14") (pin "10") (pinfunction "VSS_10") (pintype "passive"))
      (node (ref "U14") (pin "19") (pinfunction "VSSA_19") (pintype "passive"))
      (node (ref "U14") (pin "26") (pinfunction "VSS_26") (pintype "passive"))
      (node (ref "U14") (pin "49") (pinfunction "VSS_49") (pintype "passive"))
      (node (ref "U14") (pin "74") (pinfunction "VSS_74") (pintype "passive"))
      (node (ref "U14") (pin "99") (pinfunction "VSS_99") (pintype "passive"))
      (node (ref "U15") (pin "2") (pinfunction "-VS_2") (pintype "power_in"))
      (node (ref "U16") (pin "4") (pinfunction "V-_4") (pintype "passive"))
      (node (ref "U16") (pin "5") (pinfunction "NC_5") (pintype "passive"))
      (node (ref "U16") (pin "8") (pinfunction "NC_8") (pintype "passive"))
      (node (ref "U17") (pin "4") (pinfunction "V-_4") (pintype "passive"))
      (node (ref "U17") (pin "5") (pinfunction "NC_5") (pintype "passive"))
      (node (ref "U17") (pin "8") (pinfunction "NC_8") (pintype "passive"))
      (node (ref "U18") (pin "4") (pinfunction "V-_4") (pintype "passive"))
      (node (ref "U18") (pin "5") (pinfunction "NC_5") (pintype "passive"))
      (node (ref "U18") (pin "8") (pinfunction "NC_8") (pintype "passive"))
      (node (ref "U19") (pin "2") (pinfunction "GND_2") (pintype "passive"))
      (node (ref "U20") (pin "18") (pinfunction "GND_18") (pintype "passive"))
      (node (ref "U20") (pin "21") (pinfunction "GND_21") (pintype "passive"))
      (node (ref "U20") (pin "25") (pinfunction "AGND_25") (pintype "passive"))
      (node (ref "U20") (pin "26") (pinfunction "TEST_26") (pintype "input"))
      (node (ref "U20") (pin "7") (pinfunction "GND_7") (pintype "passive"))
      (node (ref "U21") (pin "2") (pinfunction "GND_2") (pintype "passive"))
      (node (ref "U22") (pin "2") (pinfunction "GND_2") (pintype "passive"))
      (node (ref "U5") (pin "2") (pinfunction "-VS_2") (pintype "power_in"))
      (node (ref "U6") (pin "4") (pinfunction "V-_4") (pintype "passive"))
      (node (ref "U6") (pin "5") (pinfunction "NC_5") (pintype "passive"))
      (node (ref "U6") (pin "8") (pinfunction "NC_8") (pintype "passive"))
      (node (ref "U7") (pin "4") (pinfunction "V-_4") (pintype "passive"))
      (node (ref "U7") (pin "5") (pinfunction "NC_5") (pintype "passive"))
      (node (ref "U7") (pin "8") (pinfunction "NC_8") (pintype "passive"))
      (node (ref "U8") (pin "4") (pinfunction "V-_4") (pintype "passive"))
      (node (ref "U8") (pin "5") (pinfunction "NC_5") (pintype "passive"))
      (node (ref "U8") (pin "8") (pinfunction "NC_8") (pintype "passive"))
      (node (ref "U9") (pin "3") (pinfunction "GND1_3") (pintype "power_in"))
      (node (ref "U9") (pin "6") (pinfunction "GND2_6") (pintype "power_in"))
    )
    (net (code "32") (name "Net-(C17-Pad1)") (class "Default")
      (node (ref "C17") (pin "1") (pinfunction "1_1") (pintype "passive"))
      (node (ref "C30") (pin "1") (pinfunction "1_1") (pintype "passive"))
      (node (ref "R18") (pin "2") (pinfunction "2_2") (pintype "passive"))
      (node (ref "R21") (pin "2") (pinfunction "2_2") (pintype "passive"))
    )
    (net (code "33") (name "Net-(C19-Pad1)") (class "Default")
      (node (ref "C19") (pin "1") (pinfunction "1_1") (pintype "passive"))
      (node (ref "C32") (pin "1") (pinfunction "1_1") (pintype "passive"))
      (node (ref "R19") (pin "2") (pinfunction "2_2") (pintype "passive"))
      (node (ref "R22") (pin "2") (pinfunction "2_2") (pintype "passive"))
    )
    (net (code "34") (name "Net-(C21-Pad1)") (class "Default")
      (node (ref "C21") (pin "1") (pinfunction "1_1") (pintype "passive"))
      (node (ref "C33") (pin "1") (pinfunction "1_1") (pintype "passive"))
      (node (ref "R20") (pin "2") (pinfunction "2_2") (pintype "passive"))
      (node (ref "R23") (pin "2") (pinfunction "2_2") (pintype "passive"))
    )
    (net (code "35") (name "Net-(C29-Pad2)") (class "Default")
      (node (ref "C29") (pin "2") (pinfunction "2_2") (pintype "passive"))
      (node (ref "R18") (pin "1") (pinfunction "1_1") (pintype "passive"))
    )
    (net (code "36") (name "Net-(C41-Pad1)") (class "Default")
      (node (ref "C41") (pin "1") (pinfunction "1_1") (pintype "passive"))
      (node (ref "C53") (pin "1") (pinfunction "1_1") (pintype "passive"))
      (node (ref "R33") (pin "2") (pinfunction "2_2") (pintype "passive"))
      (node (ref "R36") (pin "2") (pinfunction "2_2") (pintype "passive"))
    )
    (net (code "37") (name "Net-(C42-Pad1)") (class "Default")
      (node (ref "C42") (pin "1") (pinfunction "1_1") (pintype "passive"))
      (node (ref "C55") (pin "1") (pinfunction "1_1") (pintype "passive"))
      (node (ref "R34") (pin "2") (pinfunction "2_2") (pintype "passive"))
      (node (ref "R38") (pin "2") (pinfunction "2_2") (pintype "passive"))
    )
    (net (code "38") (name "Net-(C43-Pad1)") (class "Default")
      (node (ref "C43") (pin "1") (pinfunction "1_1") (pintype "passive"))
      (node (ref "C57") (pin "1") (pinfunction "1_1") (pintype "passive"))
      (node (ref "R35") (pin "2") (pinfunction "2_2") (pintype "passive"))
      (node (ref "R39") (pin "2") (pinfunction "2_2") (pintype "passive"))
    )
    (net (code "39") (name "Net-(C52-Pad2)") (class "Default")
      (node (ref "C52") (pin "2") (pinfunction "2_2") (pintype "passive"))
      (node (ref "R33") (pin "1") (pinfunction "1_1") (pintype "passive"))
    )
    (net (code "40") (name "Net-(C66-Pad1)") (class "Default")
      (node (ref "C66") (pin "1") (pinfunction "1_1") (pintype "passive"))
      (node (ref "C73") (pin "1") (pinfunction "1_1") (pintype "passive"))
      (node (ref "R46") (pin "2") (pinfunction "2_2") (pintype "passive"))
      (node (ref "R50") (pin "2") (pinfunction "2_2") (pintype "passive"))
    )
    (net (code "41") (name "Net-(C67-Pad1)") (class "Default")
      (node (ref "C67") (pin "1") (pinfunction "1_1") (pintype "passive"))
      (node (ref "C75") (pin "1") (pinfunction "1_1") (pintype "passive"))
      (node (ref "R47") (pin "2") (pinfunction "2_2") (pintype "passive"))
      (node (ref "R51") (pin "2") (pinfunction "2_2") (pintype "passive"))
    )
    (net (code "42") (name "Net-(C68-Pad1)") (class "Default")
      (node (ref "C68") (pin "1") (pinfunction "1_1") (pintype "passive"))
      (node (ref "C76") (pin "1") (pinfunction "1_1") (pintype "passive"))
      (node (ref "R48") (pin "2") (pinfunction "2_2") (pintype "passive"))
      (node (ref "R53") (pin "2") (pinfunction "2_2") (pintype "passive"))
    )
    (net (code "43") (name "Net-(C72-Pad2)") (class "Default")
      (node (ref "C72") (pin "2") (pinfunction "2_2") (pintype "passive"))
      (node (ref "R46") (pin "1") (pinfunction "1_1") (pintype "passive"))
    )
    (net (code "44") (name "Net-(D2-Pad1)") (class "Default")
      (node (ref "D2") (pin "1") (pinfunction "1_1") (pintype "passive"))
      (node (ref "R11") (pin "2") (pinfunction "2_2") (pintype "passive"))
    )
    (net (code "45") (name "Net-(D3-Pad1)") (class "Default")
      (node (ref "D3") (pin "1") (pinfunction "1_1") (pintype "passive"))
      (node (ref "R15") (pin "1") (pinfunction "1_1") (pintype "passive"))
    )
    (net (code "46") (name "Net-(D4-Pad1)") (class "Default")
      (node (ref "D4") (pin "1") (pinfunction "1_1") (pintype "passive"))
      (node (ref "R14") (pin "1") (pinfunction "1_1") (pintype "passive"))
    )
    (net (code "47") (name "Net-(D5-Pad1)") (class "Default")
      (node (ref "D5") (pin "1") (pinfunction "1_1") (pintype "passive"))
      (node (ref "R28") (pin "1") (pinfunction "1_1") (pintype "passive"))
    )
    (net (code "48") (name "Net-(D6-Pad1)") (class "Default")
      (node (ref "D6") (pin "1") (pinfunction "1_1") (pintype "passive"))
      (node (ref "R24") (pin "1") (pinfunction "1_1") (pintype "passive"))
    )
    (net (code "49") (name "Net-(D7-Pad1)") (class "Default")
      (node (ref "D7") (pin "1") (pinfunction "1_1") (pintype "passive"))
      (node (ref "R25") (pin "1") (pinfunction "1_1") (pintype "passive"))
    )
    (net (code "50") (name "Net-(D8-Pad1)") (class "Default")
      (node (ref "D8") (pin "1") (pinfunction "1_1") (pintype "passive"))
      (node (ref "R49") (pin "2") (pinfunction "2_2") (pintype "passive"))
    )
    (net (code "51") (name "Net-(D9-Pad1)") (class "Default")
      (node (ref "D9") (pin "1") (pinfunction "1_1") (pintype "passive"))
      (node (ref "R52") (pin "2") (pinfunction "2_2") (pintype "passive"))
    )
    (net (code "52") (name "Net-(D10-Pad1)") (class "Default")
      (node (ref "D10") (pin "1") (pinfunction "1_1") (pintype "passive"))
      (node (ref "R54") (pin "2") (pinfunction "2_2") (pintype "passive"))
    )
    (net (code "53") (name "Net-(D11-Pad1)") (class "Default")
      (node (ref "D11") (pin "1") (pinfunction "1_1") (pintype "passive"))
      (node (ref "R57") (pin "2") (pinfunction "2_2") (pintype "passive"))
    )
    (net (code "54") (name "Net-(D12-Pad1)") (class "Default")
      (node (ref "D12") (pin "1") (pinfunction "1_1") (pintype "passive"))
      (node (ref "R64") (pin "2") (pinfunction "2_2") (pintype "passive"))
    )
    (net (code "55") (name "Net-(D13-I{slash}O_1)") (class "Default")
      (node (ref "D13") (pin "1") (pinfunction "I/O_1_1") (pintype "passive"))
      (node (ref "R67") (pin "1") (pinfunction "1_1") (pintype "passive"))
    )
    (net (code "56") (name "Net-(D13-I{slash}O_2)") (class "Default")
      (node (ref "D13") (pin "3") (pinfunction "I/O_2_3") (pintype "passive"))
      (node (ref "R65") (pin "1") (pinfunction "1_1") (pintype "passive"))
    )
    (net (code "57") (name "Net-(D13-I{slash}O_3)") (class "Default")
      (node (ref "D13") (pin "4") (pinfunction "I/O_3_4") (pintype "passive"))
      (node (ref "J5") (pin "3") (pinfunction "D+_3") (pintype "passive"))
    )
    (net (code "58") (name "Net-(D13-I{slash}O_4)") (class "Default")
      (node (ref "D13") (pin "6") (pinfunction "I/O_4_6") (pintype "passive"))
      (node (ref "J5") (pin "2") (pinfunction "D-_2") (pintype "passive"))
    )
    (net (code "59") (name "Net-(D14-Pad1)") (class "Default")
      (node (ref "D14") (pin "1") (pinfunction "1_1") (pintype "passive"))
      (node (ref "R66") (pin "2") (pinfunction "2_2") (pintype "passive"))
    )
    (net (code "60") (name "Net-(F2-0)") (class "Default")
      (node (ref "F2") (pin "1") (pinfunction "0_1") (pintype "passive"))
      (node (ref "J4") (pin "1") (pinfunction "VCC_1") (pintype "passive"))
    )
    (net (code "61") (name "Net-(F2-1)") (class "Default")
      (node (ref "F2") (pin "2") (pinfunction "1_2") (pintype "passive"))
      (node (ref "FB3") (pin "1") (pinfunction "1_1") (pintype "passive"))
    )
    (net (code "62") (name "Net-(F3-0)") (class "Default")
      (node (ref "F3") (pin "1") (pinfunction "0_1") (pintype "passive"))
      (node (ref "FB4") (pin "2") (pinfunction "2_2") (pintype "passive"))
    )
    (net (code "63") (name "Net-(F3-1)") (class "Default")
      (node (ref "F3") (pin "2") (pinfunction "1_2") (pintype "passive"))
      (node (ref "J5") (pin "1") (pinfunction "VCC_1") (pintype "passive"))
    )
    (net (code "64") (name "Net-(J1-Ring1)") (class "Default")
      (node (ref "C29") (pin "1") (pinfunction "1_1") (pintype "passive"))
      (node (ref "J1") (pin "2") (pinfunction "Tip_2") (pintype "passive"))
      (node (ref "J1") (pin "3") (pinfunction "Ring1_3") (pintype "passive"))
      (node (ref "J1") (pin "4") (pinfunction "Ring2_4") (pintype "passive"))
      (node (ref "R13") (pin "2") (pinfunction "2_2") (pintype "passive"))
    )
    (net (code "65") (name "Net-(J2-Ring1)") (class "Default")
      (node (ref "C52") (pin "1") (pinfunction "1_1") (pintype "passive"))
      (node (ref "J2") (pin "2") (pinfunction "Tip_2") (pintype "passive"))
      (node (ref "J2") (pin "3") (pinfunction "Ring1_3") (pintype "passive"))
      (node (ref "J2") (pin "4") (pinfunction "Ring2_4") (pintype "passive"))
      (node (ref "R31") (pin "2") (pinfunction "2_2") (pintype "passive"))
    )
    (net (code "66") (name "Net-(J3-Ring1)") (class "Default")
      (node (ref "C72") (pin "1") (pinfunction "1_1") (pintype "passive"))
      (node (ref "J3") (pin "2") (pinfunction "Tip_2") (pintype "passive"))
      (node (ref "J3") (pin "3") (pinfunction "Ring1_3") (pintype "passive"))
      (node (ref "J3") (pin "4") (pinfunction "Ring2_4") (pintype "passive"))
      (node (ref "R44") (pin "2") (pinfunction "2_2") (pintype "passive"))
    )
    (net (code "67") (name "Net-(J5-ID)") (class "Default")
      (node (ref "J5") (pin "4") (pinfunction "ID_4") (pintype "passive"))
      (node (ref "R68") (pin "1") (pinfunction "1_1") (pintype "passive"))
    )
    (net (code "68") (name "Net-(U5-+IN)") (class "Default")
      (node (ref "C21") (pin "2") (pinfunction "2_2") (pintype "passive"))
      (node (ref "R16") (pin "2") (pinfunction "2_2") (pintype "passive"))
      (node (ref "U5") (pin "3") (pinfunction "+IN_3") (pintype "passive"))
      (node (ref "U8") (pin "7") (pinfunction "OUT_7") (pintype "passive"))
    )
    (net (code "69") (name "Net-(U6--IN)") (class "Default")
      (node (ref "C30") (pin "2") (pinfunction "2_2") (pintype "passive"))
      (node (ref "R10") (pin "1") (pinfunction "1_1") (pintype "passive"))
      (node (ref "U6") (pin "2") (pinfunction "-IN_2") (pintype "passive"))
    )
    (net (code "70") (name "Net-(U6-OUT)") (class "Default")
      (node (ref "C17") (pin "2") (pinfunction "2_2") (pintype "passive"))
      (node (ref "R10") (pin "2") (pinfunction "2_2") (pintype "passive"))
      (node (ref "R19") (pin "1") (pinfunction "1_1") (pintype "passive"))
      (node (ref "U6") (pin "7") (pinfunction "OUT_7") (pintype "passive"))
    )
    (net (code "71") (name "Net-(U7--IN)") (class "Default")
      (node (ref "C32") (pin "2") (pinfunction "2_2") (pintype "passive"))
      (node (ref "R12") (pin "1") (pinfunction "1_1") (pintype "passive"))
      (node (ref "U7") (pin "2") (pinfunction "-IN_2") (pintype "passive"))
    )
    (net (code "72") (name "Net-(U7-OUT)") (class "Default")
      (node (ref "C19") (pin "2") (pinfunction "2_2") (pintype "passive"))
      (node (ref "R12") (pin "2") (pinfunction "2_2") (pintype "passive"))
      (node (ref "R20") (pin "1") (pinfunction "1_1") (pintype "passive"))
      (node (ref "U7") (pin "7") (pinfunction "OUT_7") (pintype "passive"))
    )
    (net (code "73") (name "Net-(U8--IN)") (class "Default")
      (node (ref "C33") (pin "2") (pinfunction "2_2") (pintype "passive"))
      (node (ref "R16") (pin "1") (pinfunction "1_1") (pintype "passive"))
      (node (ref "U8") (pin "2") (pinfunction "-IN_2") (pintype "passive"))
    )
    (net (code "74") (name "Net-(U9-NR{slash}FB)") (class "Default")
      (node (ref "C40") (pin "2") (pinfunction "2_2") (pintype "passive"))
      (node (ref "U9") (pin "5") (pinfunction "NR/FB_5") (pintype "input"))
    )
    (net (code "75") (name "Net-(U10-+IN)") (class "Default")
      (node (ref "C43") (pin "2") (pinfunction "2_2") (pintype "passive"))
      (node (ref "R32") (pin "2") (pinfunction "2_2") (pintype "passive"))
      (node (ref "U10") (pin "3") (pinfunction "+IN_3") (pintype "passive"))
      (node (ref "U13") (pin "7") (pinfunction "OUT_7") (pintype "passive"))
    )
    (net (code "76") (name "Net-(U11--IN)") (class "Default")
      (node (ref "C53") (pin "2") (pinfunction "2_2") (pintype "passive"))
      (node (ref "R29") (pin "1") (pinfunction "1_1") (pintype "passive"))
      (node (ref "U11") (pin "2") (pinfunction "-IN_2") (pintype "passive"))
    )
    (net (code "77") (name "Net-(U11-OUT)") (class "Default")
      (node (ref "C41") (pin "2") (pinfunction "2_2") (pintype "passive"))
      (node (ref "R29") (pin "2") (pinfunction "2_2") (pintype "passive"))
      (node (ref "R34") (pin "1") (pinfunction "1_1") (pintype "passive"))
      (node (ref "U11") (pin "7") (pinfunction "OUT_7") (pintype "passive"))
    )
    (net (code "78") (name "Net-(U12--IN)") (class "Default")
      (node (ref "C55") (pin "2") (pinfunction "2_2") (pintype "passive"))
      (node (ref "R30") (pin "1") (pinfunction "1_1") (pintype "passive"))
      (node (ref "U12") (pin "2") (pinfunction "-IN_2") (pintype "passive"))
    )
    (net (code "79") (name "Net-(U12-OUT)") (class "Default")
      (node (ref "C42") (pin "2") (pinfunction "2_2") (pintype "passive"))
      (node (ref "R30") (pin "2") (pinfunction "2_2") (pintype "passive"))
      (node (ref "R35") (pin "1") (pinfunction "1_1") (pintype "passive"))
      (node (ref "U12") (pin "7") (pinfunction "OUT_7") (pintype "passive"))
    )
    (net (code "80") (name "Net-(U13--IN)") (class "Default")
      (node (ref "C57") (pin "2") (pinfunction "2_2") (pintype "passive"))
      (node (ref "R32") (pin "1") (pinfunction "1_1") (pintype "passive"))
      (node (ref "U13") (pin "2") (pinfunction "-IN_2") (pintype "passive"))
    )
    (net (code "81") (name "Net-(U14A-BOOT0)") (class "Default")
      (node (ref "R37") (pin "2") (pinfunction "2_2") (pintype "passive"))
      (node (ref "U14") (pin "94") (pinfunction "BOOT0_94") (pintype "passive"))
    )
    (net (code "82") (name "Net-(U14A-NRST)") (class "Default")
      (node (ref "C59") (pin "1") (pinfunction "1_1") (pintype "passive"))
      (node (ref "S1") (pin "1") (pinfunction "1_1") (pintype "passive"))
      (node (ref "S1") (pin "2") (pinfunction "2_2") (pintype "passive"))
      (node (ref "U14") (pin "14") (pinfunction "NRST_14") (pintype "passive"))
    )
    (net (code "83") (name "Net-(U14A-VCAP1)") (class "Default")
      (node (ref "C61") (pin "1") (pinfunction "1_1") (pintype "passive"))
      (node (ref "U14") (pin "48") (pinfunction "VCAP1_48") (pintype "passive"))
    )
    (net (code "84") (name "Net-(U14A-VCAP2)") (class "Default")
      (node (ref "C60") (pin "1") (pinfunction "1_1") (pintype "passive"))
      (node (ref "U14") (pin "73") (pinfunction "VCAP2_73") (pintype "passive"))
    )
    (net (code "85") (name "Net-(U14A-VDDA)") (class "Default")
      (node (ref "C62") (pin "2") (pinfunction "2_2") (pintype "passive"))
      (node (ref "C63") (pin "2") (pinfunction "2_2") (pintype "passive"))
      (node (ref "FB1") (pin "1") (pinfunction "1_1") (pintype "passive"))
      (node (ref "U14") (pin "20") (pinfunction "VREF+_20") (pintype "passive"))
      (node (ref "U14") (pin "21") (pinfunction "VDDA_21") (pintype "passive"))
    )
    (net (code "86") (name "Net-(U14C-PB0)") (class "Default")
      (node (ref "R49") (pin "1") (pinfunction "1_1") (pintype "passive"))
      (node (ref "U14") (pin "34") (pinfunction "PB0_34") (pintype "passive"))
    )
    (net (code "87") (name "Net-(U14C-PB1)") (class "Default")
      (node (ref "R52") (pin "1") (pinfunction "1_1") (pintype "passive"))
      (node (ref "U14") (pin "35") (pinfunction "PB1_35") (pintype "passive"))
    )
    (net (code "88") (name "Net-(U14C-PB2)") (class "Default")
      (node (ref "R54") (pin "1") (pinfunction "1_1") (pintype "passive"))
      (node (ref "U14") (pin "36") (pinfunction "PB2_36") (pintype "passive"))
    )
    (net (code "89") (name "Net-(U14C-PB3)") (class "Default")
      (node (ref "R57") (pin "1") (pinfunction "1_1") (pintype "passive"))
      (node (ref "U14") (pin "89") (pinfunction "PB3_89") (pintype "passive"))
    )
    (net (code "90") (name "Net-(U15-+IN)") (class "Default")
      (node (ref "C68") (pin "2") (pinfunction "2_2") (pintype "passive"))
      (node (ref "R45") (pin "2") (pinfunction "2_2") (pintype "passive"))
      (node (ref "U15") (pin "3") (pinfunction "+IN_3") (pintype "passive"))
      (node (ref "U18") (pin "7") (pinfunction "OUT_7") (pintype "passive"))
    )
    (net (code "91") (name "Net-(U16--IN)") (class "Default")
      (node (ref "C73") (pin "2") (pinfunction "2_2") (pintype "passive"))
      (node (ref "R42") (pin "1") (pinfunction "1_1") (pintype "passive"))
      (node (ref "U16") (pin "2") (pinfunction "-IN_2") (pintype "passive"))
    )
    (net (code "92") (name "Net-(U16-OUT)") (class "Default")
      (node (ref "C66") (pin "2") (pinfunction "2_2") (pintype "passive"))
      (node (ref "R42") (pin "2") (pinfunction "2_2") (pintype "passive"))
      (node (ref "R47") (pin "1") (pinfunction "1_1") (pintype "passive"))
      (node (ref "U16") (pin "7") (pinfunction "OUT_7") (pintype "passive"))
    )
    (net (code "93") (name "Net-(U17--IN)") (class "Default")
      (node (ref "C75") (pin "2") (pinfunction "2_2") (pintype "passive"))
      (node (ref "R43") (pin "1") (pinfunction "1_1") (pintype "passive"))
      (node (ref "U17") (pin "2") (pinfunction "-IN_2") (pintype "passive"))
    )
    (net (code "94") (name "Net-(U17-OUT)") (class "Default")
      (node (ref "C67") (pin "2") (pinfunction "2_2") (pintype "passive"))
      (node (ref "R43") (pin "2") (pinfunction "2_2") (pintype "passive"))
      (node (ref "R48") (pin "1") (pinfunction "1_1") (pintype "passive"))
      (node (ref "U17") (pin "7") (pinfunction "OUT_7") (pintype "passive"))
    )
    (net (code "95") (name "Net-(U18--IN)") (class "Default")
      (node (ref "C76") (pin "2") (pinfunction "2_2") (pintype "passive"))
      (node (ref "R45") (pin "1") (pinfunction "1_1") (pintype "passive"))
      (node (ref "U18") (pin "2") (pinfunction "-IN_2") (pintype "passive"))
    )
    (net (code "96") (name "Net-(U20-3V3OUT)") (class "Default")
      (node (ref "C82") (pin "2") (pinfunction "2_2") (pintype "passive"))
      (node (ref "P3") (pin "3") (pinfunction "3_3") (pintype "passive"))
      (node (ref "U20") (pin "17") (pinfunction "3V3OUT_17") (pintype "output"))
    )
    (net (code "97") (name "Net-(U20-CBUS0)") (class "Default")
      (node (ref "D12") (pin "2") (pinfunction "2_2") (pintype "passive"))
      (node (ref "U20") (pin "23") (pinfunction "CBUS0_23") (pintype "bidirectional"))
    )
    (net (code "98") (name "Net-(U20-CBUS1)") (class "Default")
      (node (ref "D14") (pin "2") (pinfunction "2_2") (pintype "passive"))
      (node (ref "U20") (pin "22") (pinfunction "CBUS1_22") (pintype "bidirectional"))
    )
    (net (code "99") (name "Net-(U20-VCCIO)") (class "Default")
      (node (ref "P3") (pin "2") (pinfunction "2_2") (pintype "passive"))
      (node (ref "U20") (pin "4") (pinfunction "VCCIO_4") (pintype "power_in"))
    )
    (net (code "100") (name "REF1") (class "Default")
      (node (ref "C77") (pin "2") (pinfunction "2_2") (pintype "passive"))
      (node (ref "R21") (pin "1") (pinfunction "1_1") (pintype "passive"))
      (node (ref "R22") (pin "1") (pinfunction "1_1") (pintype "passive"))
      (node (ref "R23") (pin "1") (pinfunction "1_1") (pintype "passive"))
      (node (ref "U19") (pin "1") (pinfunction "V_BIAS_1") (pintype "passive"))
      (node (ref "U6") (pin "3") (pinfunction "+IN_3") (pintype "passive"))
      (node (ref "U7") (pin "3") (pinfunction "+IN_3") (pintype "passive"))
      (node (ref "U8") (pin "3") (pinfunction "+IN_3") (pintype "passive"))
    )
    (net (code "101") (name "REF2") (class "Default")
      (node (ref "C83") (pin "2") (pinfunction "2_2") (pintype "passive"))
      (node (ref "R36") (pin "1") (pinfunction "1_1") (pintype "passive"))
      (node (ref "R38") (pin "1") (pinfunction "1_1") (pintype "passive"))
      (node (ref "R39") (pin "1") (pinfunction "1_1") (pintype "passive"))
      (node (ref "U11") (pin "3") (pinfunction "+IN_3") (pintype "passive"))
      (node (ref "U12") (pin "3") (pinfunction "+IN_3") (pintype "passive"))
      (node (ref "U13") (pin "3") (pinfunction "+IN_3") (pintype "passive"))
      (node (ref "U21") (pin "1") (pinfunction "V_BIAS_1") (pintype "passive"))
    )
    (net (code "102") (name "REF3") (class "Default")
      (node (ref "C86") (pin "2") (pinfunction "2_2") (pintype "passive"))
      (node (ref "R50") (pin "1") (pinfunction "1_1") (pintype "passive"))
      (node (ref "R51") (pin "1") (pinfunction "1_1") (pintype "passive"))
      (node (ref "R53") (pin "1") (pinfunction "1_1") (pintype "passive"))
      (node (ref "U16") (pin "3") (pinfunction "+IN_3") (pintype "passive"))
      (node (ref "U17") (pin "3") (pinfunction "+IN_3") (pintype "passive"))
      (node (ref "U18") (pin "3") (pinfunction "+IN_3") (pintype "passive"))
      (node (ref "U22") (pin "1") (pinfunction "V_BIAS_1") (pintype "passive"))
    )
    (net (code "103") (name "V_IN") (class "Default")
      (node (ref "C34") (pin "1") (pinfunction "1_1") (pintype "passive"))
      (node (ref "C35") (pin "1") (pinfunction "1_1") (pintype "passive"))
      (node (ref "R15") (pin "2") (pinfunction "2_2") (pintype "passive"))
    )
    (net (code "104") (name "unconnected-(J4-ID-Pad4)") (class "Default")
      (node (ref "J4") (pin "4") (pinfunction "ID_4") (pintype "passive"))
    )
    (net (code "105") (name "unconnected-(U6-NC-Pad1)") (class "Default")
      (node (ref "U6") (pin "1") (pinfunction "NC_1") (pintype "passive"))
    )
    (net (code "106") (name "unconnected-(U7-NC-Pad1)") (class "Default")
      (node (ref "U7") (pin "1") (pinfunction "NC_1") (pintype "passive"))
    )
    (net (code "107") (name "unconnected-(U8-NC-Pad1)") (class "Default")
      (node (ref "U8") (pin "1") (pinfunction "NC_1") (pintype "passive"))
    )
    (net (code "108") (name "unconnected-(U11-NC-Pad1)") (class "Default")
      (node (ref "U11") (pin "1") (pinfunction "NC_1") (pintype "passive"))
    )
    (net (code "109") (name "unconnected-(U12-NC-Pad1)") (class "Default")
      (node (ref "U12") (pin "1") (pinfunction "NC_1") (pintype "passive"))
    )
    (net (code "110") (name "unconnected-(U13-NC-Pad1)") (class "Default")
      (node (ref "U13") (pin "1") (pinfunction "NC_1") (pintype "passive"))
    )
    (net (code "111") (name "unconnected-(U14A-PH0-OSC_IN-Pad12)") (class "Default")
      (node (ref "U14") (pin "12") (pinfunction "PH0-OSC_IN_12") (pintype "passive"))
    )
    (net (code "112") (name "unconnected-(U14A-PH1-OSC_OUT-Pad13)") (class "Default")
      (node (ref "U14") (pin "13") (pinfunction "PH1-OSC_OUT_13") (pintype "passive"))
    )
    (net (code "113") (name "unconnected-(U14C-PA0-Pad22)") (class "Default")
      (node (ref "U14") (pin "22") (pinfunction "PA0_22") (pintype "passive"))
    )
    (net (code "114") (name "unconnected-(U14C-PA1-Pad23)") (class "Default")
      (node (ref "U14") (pin "23") (pinfunction "PA1_23") (pintype "passive"))
    )
    (net (code "115") (name "unconnected-(U14C-PA2-Pad24)") (class "Default")
      (node (ref "U14") (pin "24") (pinfunction "PA2_24") (pintype "passive"))
    )
    (net (code "116") (name "unconnected-(U14C-PA3-Pad25)") (class "Default")
      (node (ref "U14") (pin "25") (pinfunction "PA3_25") (pintype "passive"))
    )
    (net (code "117") (name "unconnected-(U14C-PA4-Pad28)") (class "Default")
      (node (ref "U14") (pin "28") (pinfunction "PA4_28") (pintype "passive"))
    )
    (net (code "118") (name "unconnected-(U14C-PA5-Pad29)") (class "Default")
      (node (ref "U14") (pin "29") (pinfunction "PA5_29") (pintype "passive"))
    )
    (net (code "119") (name "unconnected-(U14C-PA6-Pad30)") (class "Default")
      (node (ref "U14") (pin "30") (pinfunction "PA6_30") (pintype "passive"))
    )
    (net (code "120") (name "unconnected-(U14C-PA7-Pad31)") (class "Default")
      (node (ref "U14") (pin "31") (pinfunction "PA7_31") (pintype "passive"))
    )
    (net (code "121") (name "unconnected-(U14C-PA8-Pad67)") (class "Default")
      (node (ref "U14") (pin "67") (pinfunction "PA8_67") (pintype "passive"))
    )
    (net (code "122") (name "unconnected-(U14C-PA15-Pad77)") (class "Default")
      (node (ref "U14") (pin "77") (pinfunction "PA15_77") (pintype "passive"))
    )
    (net (code "123") (name "unconnected-(U14C-PB4-Pad90)") (class "Default")
      (node (ref "U14") (pin "90") (pinfunction "PB4_90") (pintype "passive"))
    )
    (net (code "124") (name "unconnected-(U14C-PB5-Pad91)") (class "Default")
      (node (ref "U14") (pin "91") (pinfunction "PB5_91") (pintype "passive"))
    )
    (net (code "125") (name "unconnected-(U14C-PB6-Pad92)") (class "Default")
      (node (ref "U14") (pin "92") (pinfunction "PB6_92") (pintype "passive"))
    )
    (net (code "126") (name "unconnected-(U14C-PB7-Pad93)") (class "Default")
      (node (ref "U14") (pin "93") (pinfunction "PB7_93") (pintype "passive"))
    )
    (net (code "127") (name "unconnected-(U14C-PB8-Pad95)") (class "Default")
      (node (ref "U14") (pin "95") (pinfunction "PB8_95") (pintype "passive"))
    )
    (net (code "128") (name "unconnected-(U14C-PB9-Pad96)") (class "Default")
      (node (ref "U14") (pin "96") (pinfunction "PB9_96") (pintype "passive"))
    )
    (net (code "129") (name "unconnected-(U14C-PB14-Pad53)") (class "Default")
      (node (ref "U14") (pin "53") (pinfunction "PB14_53") (pintype "passive"))
    )
    (net (code "130") (name "unconnected-(U14C-PB15-Pad54)") (class "Default")
      (node (ref "U14") (pin "54") (pinfunction "PB15_54") (pintype "passive"))
    )
    (net (code "131") (name "unconnected-(U14C-PC3-Pad18)") (class "Default")
      (node (ref "U14") (pin "18") (pinfunction "PC3_18") (pintype "passive"))
    )
    (net (code "132") (name "unconnected-(U14C-PC4-Pad32)") (class "Default")
      (node (ref "U14") (pin "32") (pinfunction "PC4_32") (pintype "passive"))
    )
    (net (code "133") (name "unconnected-(U14C-PC5-Pad33)") (class "Default")
      (node (ref "U14") (pin "33") (pinfunction "PC5_33") (pintype "passive"))
    )
    (net (code "134") (name "unconnected-(U14C-PC6-Pad63)") (class "Default")
      (node (ref "U14") (pin "63") (pinfunction "PC6_63") (pintype "passive"))
    )
    (net (code "135") (name "unconnected-(U14C-PC7-Pad64)") (class "Default")
      (node (ref "U14") (pin "64") (pinfunction "PC7_64") (pintype "passive"))
    )
    (net (code "136") (name "unconnected-(U14C-PC8-Pad65)") (class "Default")
      (node (ref "U14") (pin "65") (pinfunction "PC8_65") (pintype "passive"))
    )
    (net (code "137") (name "unconnected-(U14C-PC9-Pad66)") (class "Default")
      (node (ref "U14") (pin "66") (pinfunction "PC9_66") (pintype "passive"))
    )
    (net (code "138") (name "unconnected-(U14C-PC10-Pad78)") (class "Default")
      (node (ref "U14") (pin "78") (pinfunction "PC10_78") (pintype "passive"))
    )
    (net (code "139") (name "unconnected-(U14C-PC11-Pad79)") (class "Default")
      (node (ref "U14") (pin "79") (pinfunction "PC11_79") (pintype "passive"))
    )
    (net (code "140") (name "unconnected-(U14C-PC12-Pad80)") (class "Default")
      (node (ref "U14") (pin "80") (pinfunction "PC12_80") (pintype "passive"))
    )
    (net (code "141") (name "unconnected-(U14C-PC13-Pad7)") (class "Default")
      (node (ref "U14") (pin "7") (pinfunction "PC13_7") (pintype "passive"))
    )
    (net (code "142") (name "unconnected-(U14C-PC14-OSC32_IN-Pad8)") (class "Default")
      (node (ref "U14") (pin "8") (pinfunction "PC14-OSC32_IN_8") (pintype "passive"))
    )
    (net (code "143") (name "unconnected-(U14C-PC15-OSC32_OUT-Pad9)") (class "Default")
      (node (ref "U14") (pin "9") (pinfunction "PC15-OSC32_OUT_9") (pintype "passive"))
    )
    (net (code "144") (name "unconnected-(U16-NC-Pad1)") (class "Default")
      (node (ref "U16") (pin "1") (pinfunction "NC_1") (pintype "passive"))
    )
    (net (code "145") (name "unconnected-(U17-NC-Pad1)") (class "Default")
      (node (ref "U17") (pin "1") (pinfunction "NC_1") (pintype "passive"))
    )
    (net (code "146") (name "unconnected-(U18-NC-Pad1)") (class "Default")
      (node (ref "U18") (pin "1") (pinfunction "NC_1") (pintype "passive"))
    )
    (net (code "147") (name "unconnected-(U19-V_REF-Pad5)") (class "Default")
      (node (ref "U19") (pin "5") (pinfunction "V_REF_5") (pintype "passive"))
    )
    (net (code "148") (name "unconnected-(U20-CBUS2-Pad13)") (class "Default")
      (node (ref "U20") (pin "13") (pinfunction "CBUS2_13") (pintype "bidirectional"))
    )
    (net (code "149") (name "unconnected-(U20-CBUS3-Pad14)") (class "Default")
      (node (ref "U20") (pin "14") (pinfunction "CBUS3_14") (pintype "bidirectional"))
    )
    (net (code "150") (name "unconnected-(U20-CBUS4-Pad12)") (class "Default")
      (node (ref "U20") (pin "12") (pinfunction "CBUS4_12") (pintype "bidirectional"))
    )
    (net (code "151") (name "unconnected-(U20-OSCI-Pad27)") (class "Default")
      (node (ref "U20") (pin "27") (pinfunction "OSCI_27") (pintype "input"))
    )
    (net (code "152") (name "unconnected-(U20-OSCO-Pad28)") (class "Default")
      (node (ref "U20") (pin "28") (pinfunction "OSCO_28") (pintype "output"))
    )
    (net (code "153") (name "unconnected-(U20-~{CTS}-Pad11)") (class "Default")
      (node (ref "U20") (pin "11") (pinfunction "~{CTS}_11") (pintype "input"))
    )
    (net (code "154") (name "unconnected-(U20-~{DCD}-Pad10)") (class "Default")
      (node (ref "U20") (pin "10") (pinfunction "~{DCD}_10") (pintype "input"))
    )
    (net (code "155") (name "unconnected-(U20-~{DSR}-Pad9)") (class "Default")
      (node (ref "U20") (pin "9") (pinfunction "~{DSR}_9") (pintype "input"))
    )
    (net (code "156") (name "unconnected-(U20-~{DTR}-Pad2)") (class "Default")
      (node (ref "U20") (pin "2") (pinfunction "~{DTR}_2") (pintype "output"))
    )
    (net (code "157") (name "unconnected-(U20-~{RESET}-Pad19)") (class "Default")
      (node (ref "U20") (pin "19") (pinfunction "~{RESET}_19") (pintype "input"))
    )
    (net (code "158") (name "unconnected-(U20-~{RI}-Pad6)") (class "Default")
      (node (ref "U20") (pin "6") (pinfunction "~{RI}_6") (pintype "input"))
    )
    (net (code "159") (name "unconnected-(U20-~{RTS}-Pad3)") (class "Default")
      (node (ref "U20") (pin "3") (pinfunction "~{RTS}_3") (pintype "output"))
    )
    (net (code "160") (name "unconnected-(U21-V_REF-Pad5)") (class "Default")
      (node (ref "U21") (pin "5") (pinfunction "V_REF_5") (pintype "passive"))
    )
    (net (code "161") (name "unconnected-(U22-V_REF-Pad5)") (class "Default")
      (node (ref "U22") (pin "5") (pinfunction "V_REF_5") (pintype "passive"))
    )
  )
)
